# Mikrolysreklamen17.net
KiCad netlist of a schematic drawn in Altium Designer
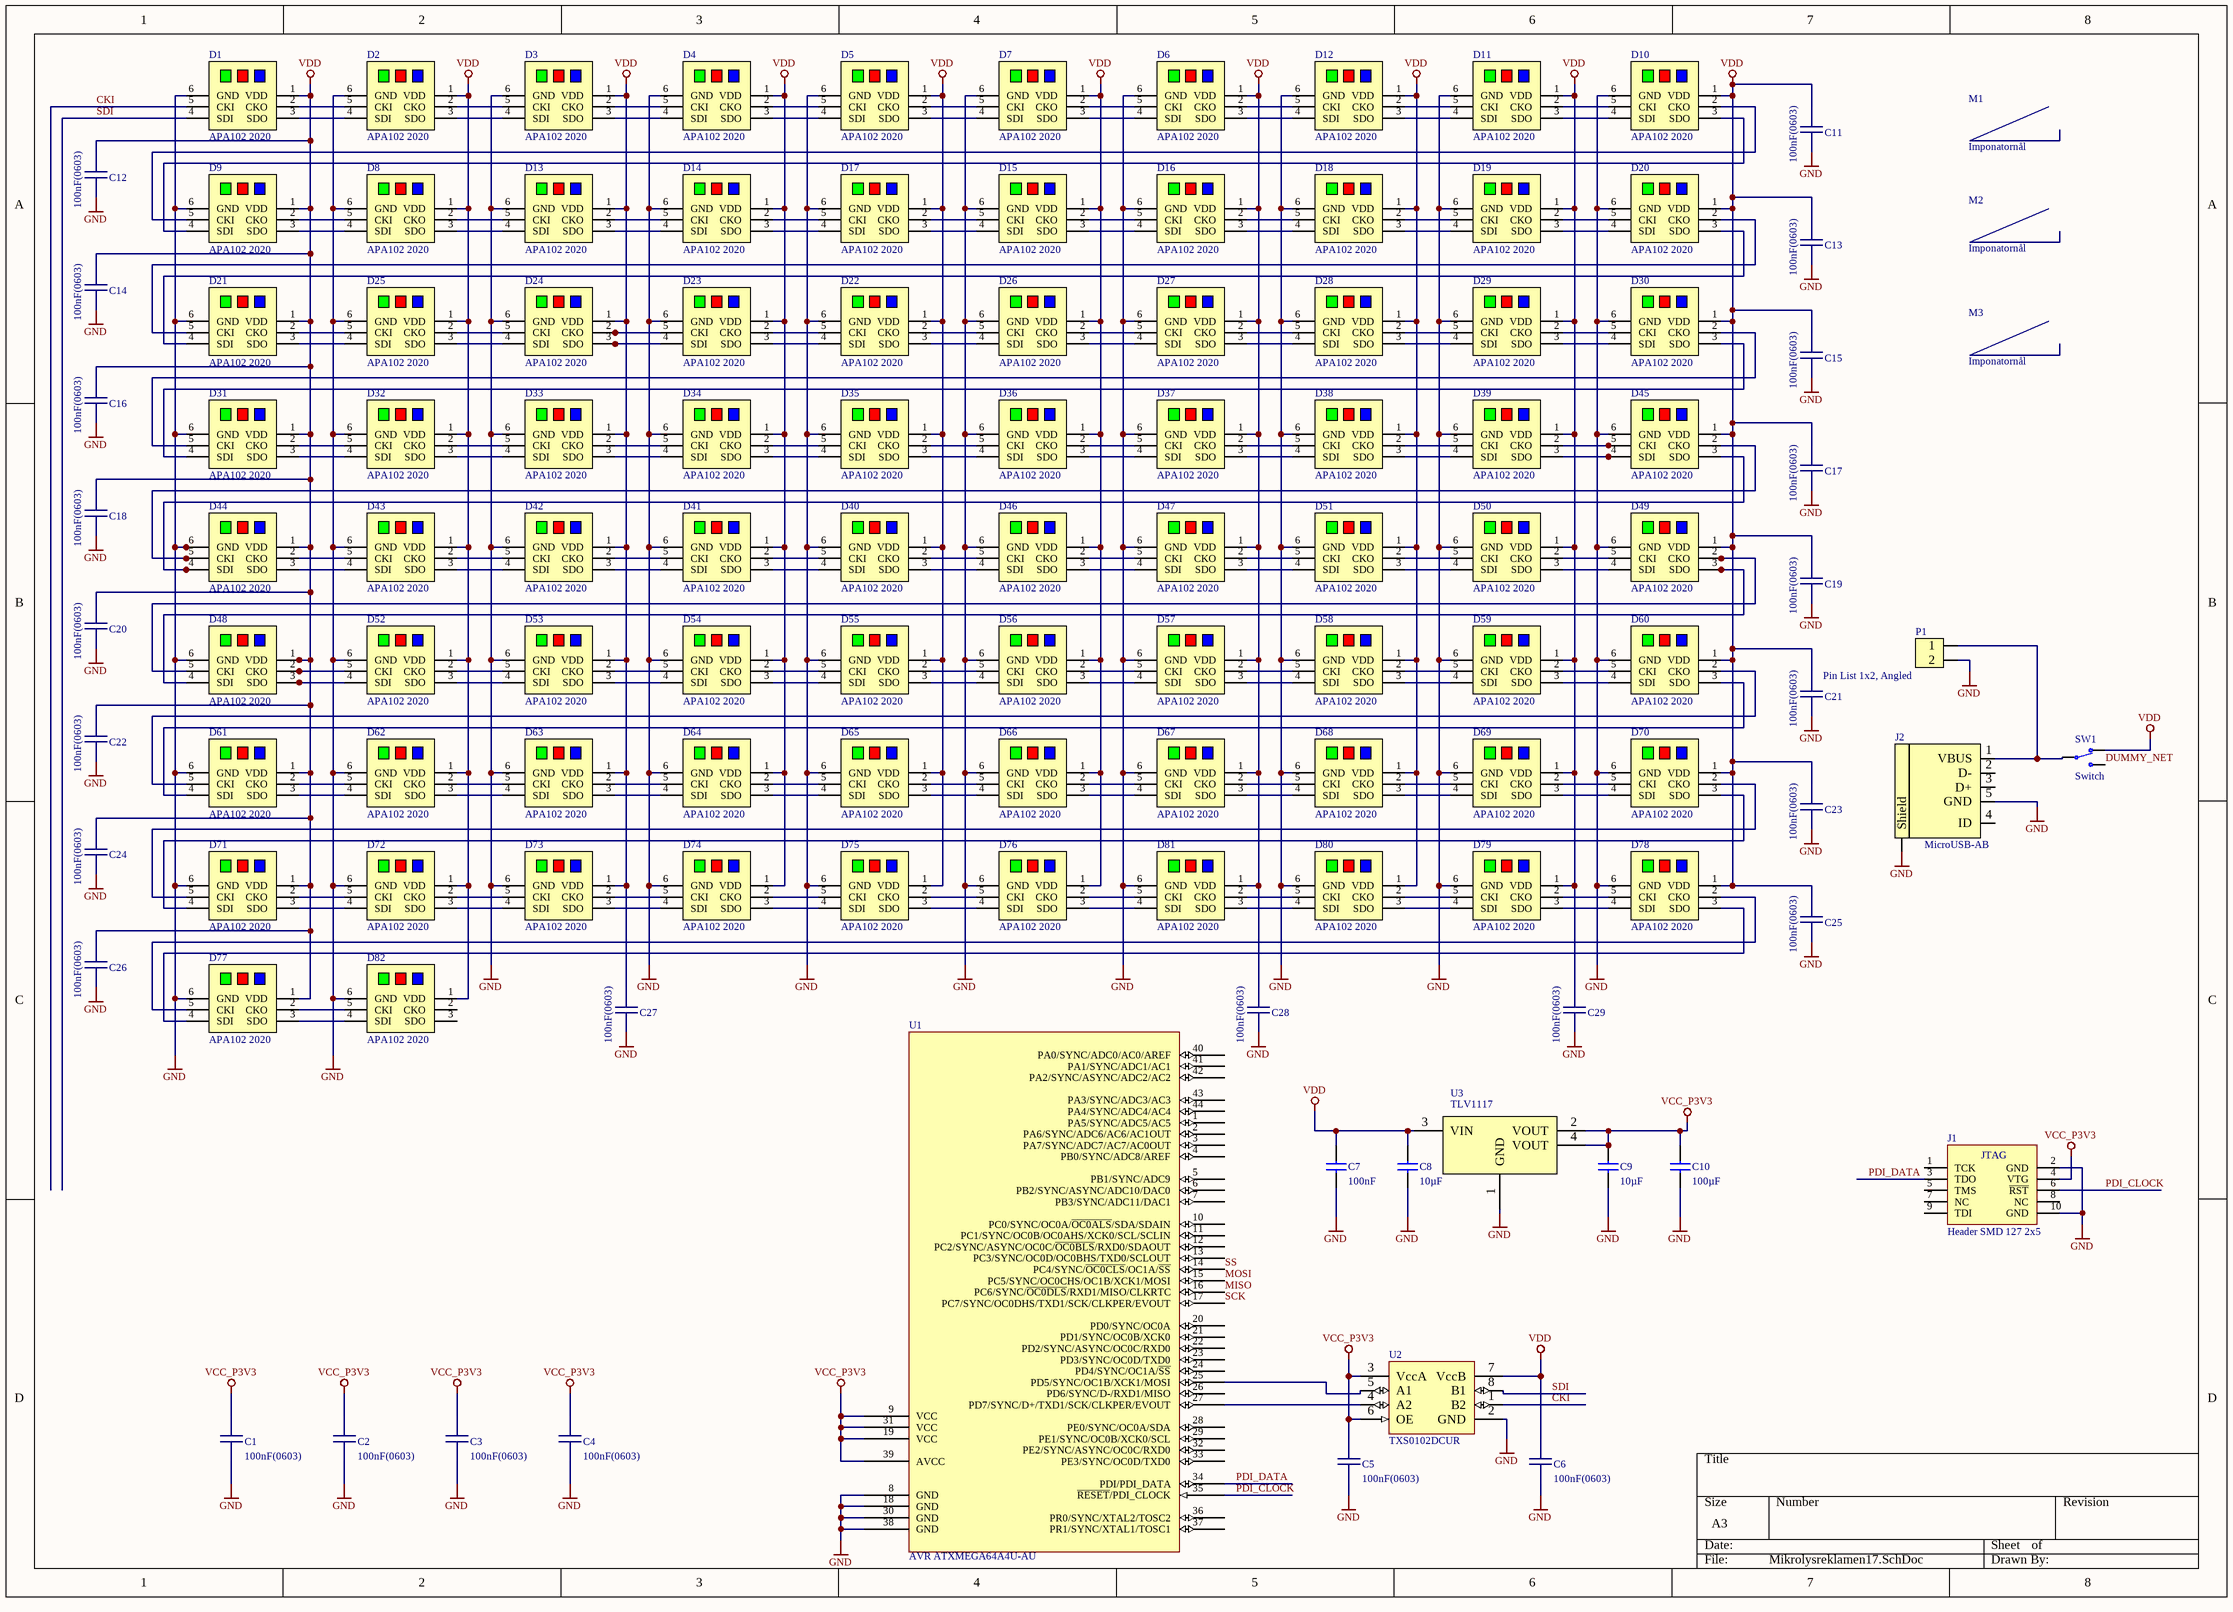
[diagram p0: Mikrolysreklamen17.SchDoc]

(export (version "E")
  (design (tool "Eeschema 10.0.6"))
  (components
    (comp (ref "C1")
      (value "100nF(0603)")
      (footprint "CAPC0603(1608)55_N")
      (description "100nF 0603 5% X7R 50V")
      (libsource (lib "OVLib") (part "CAP"))
    )
    (comp (ref "C2")
      (value "100nF(0603)")
      (footprint "CAPC0603(1608)55_N")
      (description "100nF 0603 5% X7R 50V")
      (libsource (lib "OVLib") (part "CAP"))
    )
    (comp (ref "C3")
      (value "100nF(0603)")
      (footprint "CAPC0603(1608)55_N")
      (description "100nF 0603 5% X7R 50V")
      (libsource (lib "OVLib") (part "CAP"))
    )
    (comp (ref "C4")
      (value "100nF(0603)")
      (footprint "CAPC0603(1608)55_N")
      (description "100nF 0603 5% X7R 50V")
      (libsource (lib "OVLib") (part "CAP"))
    )
    (comp (ref "C5")
      (value "100nF(0603)")
      (footprint "CAPC0603(1608)55_N")
      (description "100nF 0603 5% X7R 50V")
      (libsource (lib "OVLib") (part "CAP"))
    )
    (comp (ref "C6")
      (value "100nF(0603)")
      (footprint "CAPC0603(1608)55_N")
      (description "100nF 0603 5% X7R 50V")
      (libsource (lib "OVLib") (part "CAP"))
    )
    (comp (ref "C7")
      (value "100nF")
      (footprint "CAPC1005X04L")
      (description "Capacitor, X7R, ±10%")
      (fields (field (name "PART NUMBER") "C0402-100n") (field (name "PUBLISHER") "Nordic Semiconductor"))
      (libsource (lib "Nordic Passive DB") (part "CAP"))
    )
    (comp (ref "C8")
      (value "10µF")
      (footprint "CAPC1608X06L")
      (description "Capacitor, X5R, ±20%")
      (fields (field (name "PART NUMBER") "C0603-10µ") (field (name "PUBLISHER") "Nordic Semiconductor"))
      (libsource (lib "Nordic Passive DB") (part "CAP"))
    )
    (comp (ref "C9")
      (value "10µF")
      (footprint "CAPC1608X06L")
      (description "Capacitor, X5R, ±20%")
      (fields (field (name "PART NUMBER") "C0603-10µ") (field (name "PUBLISHER") "Nordic Semiconductor"))
      (libsource (lib "Nordic Passive DB") (part "CAP"))
    )
    (comp (ref "C10")
      (value "100µF")
      (footprint "CAPC2012X11L")
      (description "Chip Cap 0805")
      (fields (field (name "PART NUMBER") "C0805-TBD") (field (name "PUBLISHER") "Nordic Semiconductor"))
      (libsource (lib "Nordic Passive DB") (part "CAP"))
    )
    (comp (ref "C11")
      (value "100nF(0603)")
      (footprint "CAPC0603(1608)55_N")
      (description "100nF 0603 5% X7R 50V")
      (libsource (lib "OVLib_64") (part "CAP"))
    )
    (comp (ref "C12")
      (value "100nF(0603)")
      (footprint "CAPC0603(1608)55_N")
      (description "100nF 0603 5% X7R 50V")
      (libsource (lib "OVLib_64") (part "CAP"))
    )
    (comp (ref "C13")
      (value "100nF(0603)")
      (footprint "CAPC0603(1608)55_N")
      (description "100nF 0603 5% X7R 50V")
      (libsource (lib "OVLib_64") (part "CAP"))
    )
    (comp (ref "C14")
      (value "100nF(0603)")
      (footprint "CAPC0603(1608)55_N")
      (description "100nF 0603 5% X7R 50V")
      (libsource (lib "OVLib_64") (part "CAP"))
    )
    (comp (ref "C15")
      (value "100nF(0603)")
      (footprint "CAPC0603(1608)55_N")
      (description "100nF 0603 5% X7R 50V")
      (libsource (lib "OVLib_64") (part "CAP"))
    )
    (comp (ref "C16")
      (value "100nF(0603)")
      (footprint "CAPC0603(1608)55_N")
      (description "100nF 0603 5% X7R 50V")
      (libsource (lib "OVLib_64") (part "CAP"))
    )
    (comp (ref "C17")
      (value "100nF(0603)")
      (footprint "CAPC0603(1608)55_N")
      (description "100nF 0603 5% X7R 50V")
      (libsource (lib "OVLib_64") (part "CAP"))
    )
    (comp (ref "C18")
      (value "100nF(0603)")
      (footprint "CAPC0603(1608)55_N")
      (description "100nF 0603 5% X7R 50V")
      (libsource (lib "OVLib_64") (part "CAP"))
    )
    (comp (ref "C19")
      (value "100nF(0603)")
      (footprint "CAPC0603(1608)55_N")
      (description "100nF 0603 5% X7R 50V")
      (libsource (lib "OVLib_64") (part "CAP"))
    )
    (comp (ref "C20")
      (value "100nF(0603)")
      (footprint "CAPC0603(1608)55_N")
      (description "100nF 0603 5% X7R 50V")
      (libsource (lib "OVLib_64") (part "CAP"))
    )
    (comp (ref "C21")
      (value "100nF(0603)")
      (footprint "CAPC0603(1608)55_N")
      (description "100nF 0603 5% X7R 50V")
      (libsource (lib "OVLib_64") (part "CAP"))
    )
    (comp (ref "C22")
      (value "100nF(0603)")
      (footprint "CAPC0603(1608)55_N")
      (description "100nF 0603 5% X7R 50V")
      (libsource (lib "OVLib_64") (part "CAP"))
    )
    (comp (ref "C23")
      (value "100nF(0603)")
      (footprint "CAPC0603(1608)55_N")
      (description "100nF 0603 5% X7R 50V")
      (libsource (lib "OVLib_64") (part "CAP"))
    )
    (comp (ref "C24")
      (value "100nF(0603)")
      (footprint "CAPC0603(1608)55_N")
      (description "100nF 0603 5% X7R 50V")
      (libsource (lib "OVLib_64") (part "CAP"))
    )
    (comp (ref "C25")
      (value "100nF(0603)")
      (footprint "CAPC0603(1608)55_N")
      (description "100nF 0603 5% X7R 50V")
      (libsource (lib "OVLib_64") (part "CAP"))
    )
    (comp (ref "C26")
      (value "100nF(0603)")
      (footprint "CAPC0603(1608)55_N")
      (description "100nF 0603 5% X7R 50V")
      (libsource (lib "OVLib_64") (part "CAP"))
    )
    (comp (ref "C27")
      (value "100nF(0603)")
      (footprint "CAPC0603(1608)55_N")
      (description "100nF 0603 5% X7R 50V")
      (libsource (lib "OVLib_64") (part "CAP"))
    )
    (comp (ref "C28")
      (value "100nF(0603)")
      (footprint "CAPC0603(1608)55_N")
      (description "100nF 0603 5% X7R 50V")
      (libsource (lib "OVLib_64") (part "CAP"))
    )
    (comp (ref "C29")
      (value "100nF(0603)")
      (footprint "CAPC0603(1608)55_N")
      (description "100nF 0603 5% X7R 50V")
      (libsource (lib "OVLib_64") (part "CAP"))
    )
    (comp (ref "D1")
      (value "APA102 2020")
      (footprint "PCBComponent_1")
      (libsource (lib "Schlib1") (part "APA102_2020"))
    )
    (comp (ref "D2")
      (value "APA102 2020")
      (footprint "PCBComponent_1")
      (libsource (lib "Schlib1") (part "APA102_2020"))
    )
    (comp (ref "D3")
      (value "APA102 2020")
      (footprint "PCBComponent_1")
      (libsource (lib "Schlib1") (part "APA102_2020"))
    )
    (comp (ref "D4")
      (value "APA102 2020")
      (footprint "PCBComponent_1")
      (libsource (lib "Schlib1") (part "APA102_2020"))
    )
    (comp (ref "D5")
      (value "APA102 2020")
      (footprint "PCBComponent_1")
      (libsource (lib "Schlib1") (part "APA102_2020"))
    )
    (comp (ref "D6")
      (value "APA102 2020")
      (footprint "PCBComponent_1")
      (libsource (lib "Schlib1") (part "APA102_2020"))
    )
    (comp (ref "D7")
      (value "APA102 2020")
      (footprint "PCBComponent_1")
      (libsource (lib "Schlib1") (part "APA102_2020"))
    )
    (comp (ref "D8")
      (value "APA102 2020")
      (footprint "PCBComponent_1")
      (libsource (lib "Schlib1") (part "APA102_2020"))
    )
    (comp (ref "D9")
      (value "APA102 2020")
      (footprint "PCBComponent_1")
      (libsource (lib "Schlib1") (part "APA102_2020"))
    )
    (comp (ref "D10")
      (value "APA102 2020")
      (footprint "PCBComponent_1")
      (libsource (lib "Schlib1") (part "APA102_2020"))
    )
    (comp (ref "D11")
      (value "APA102 2020")
      (footprint "PCBComponent_1")
      (libsource (lib "Schlib1") (part "APA102_2020"))
    )
    (comp (ref "D12")
      (value "APA102 2020")
      (footprint "PCBComponent_1")
      (libsource (lib "Schlib1") (part "APA102_2020"))
    )
    (comp (ref "D13")
      (value "APA102 2020")
      (footprint "PCBComponent_1")
      (libsource (lib "Schlib1") (part "APA102_2020"))
    )
    (comp (ref "D14")
      (value "APA102 2020")
      (footprint "PCBComponent_1")
      (libsource (lib "Schlib1") (part "APA102_2020"))
    )
    (comp (ref "D15")
      (value "APA102 2020")
      (footprint "PCBComponent_1")
      (libsource (lib "Schlib1") (part "APA102_2020"))
    )
    (comp (ref "D16")
      (value "APA102 2020")
      (footprint "PCBComponent_1")
      (libsource (lib "Schlib1") (part "APA102_2020"))
    )
    (comp (ref "D17")
      (value "APA102 2020")
      (footprint "PCBComponent_1")
      (libsource (lib "Schlib1") (part "APA102_2020"))
    )
    (comp (ref "D18")
      (value "APA102 2020")
      (footprint "PCBComponent_1")
      (libsource (lib "Schlib1") (part "APA102_2020"))
    )
    (comp (ref "D19")
      (value "APA102 2020")
      (footprint "PCBComponent_1")
      (libsource (lib "Schlib1") (part "APA102_2020"))
    )
    (comp (ref "D20")
      (value "APA102 2020")
      (footprint "PCBComponent_1")
      (libsource (lib "Schlib1") (part "APA102_2020"))
    )
    (comp (ref "D21")
      (value "APA102 2020")
      (footprint "PCBComponent_1")
      (libsource (lib "Schlib1") (part "APA102_2020"))
    )
    (comp (ref "D22")
      (value "APA102 2020")
      (footprint "PCBComponent_1")
      (libsource (lib "Schlib1") (part "APA102_2020"))
    )
    (comp (ref "D23")
      (value "APA102 2020")
      (footprint "PCBComponent_1")
      (libsource (lib "Schlib1") (part "APA102_2020"))
    )
    (comp (ref "D24")
      (value "APA102 2020")
      (footprint "PCBComponent_1")
      (libsource (lib "Schlib1") (part "APA102_2020"))
    )
    (comp (ref "D25")
      (value "APA102 2020")
      (footprint "PCBComponent_1")
      (libsource (lib "Schlib1") (part "APA102_2020"))
    )
    (comp (ref "D26")
      (value "APA102 2020")
      (footprint "PCBComponent_1")
      (libsource (lib "Schlib1") (part "APA102_2020"))
    )
    (comp (ref "D27")
      (value "APA102 2020")
      (footprint "PCBComponent_1")
      (libsource (lib "Schlib1") (part "APA102_2020"))
    )
    (comp (ref "D28")
      (value "APA102 2020")
      (footprint "PCBComponent_1")
      (libsource (lib "Schlib1") (part "APA102_2020"))
    )
    (comp (ref "D29")
      (value "APA102 2020")
      (footprint "PCBComponent_1")
      (libsource (lib "Schlib1") (part "APA102_2020"))
    )
    (comp (ref "D30")
      (value "APA102 2020")
      (footprint "PCBComponent_1")
      (libsource (lib "Schlib1") (part "APA102_2020"))
    )
    (comp (ref "D31")
      (value "APA102 2020")
      (footprint "PCBComponent_1")
      (libsource (lib "Schlib1") (part "APA102_2020"))
    )
    (comp (ref "D32")
      (value "APA102 2020")
      (footprint "PCBComponent_1")
      (libsource (lib "Schlib1") (part "APA102_2020"))
    )
    (comp (ref "D33")
      (value "APA102 2020")
      (footprint "PCBComponent_1")
      (libsource (lib "Schlib1") (part "APA102_2020"))
    )
    (comp (ref "D34")
      (value "APA102 2020")
      (footprint "PCBComponent_1")
      (libsource (lib "Schlib1") (part "APA102_2020"))
    )
    (comp (ref "D35")
      (value "APA102 2020")
      (footprint "PCBComponent_1")
      (libsource (lib "Schlib1") (part "APA102_2020"))
    )
    (comp (ref "D36")
      (value "APA102 2020")
      (footprint "PCBComponent_1")
      (libsource (lib "Schlib1") (part "APA102_2020"))
    )
    (comp (ref "D37")
      (value "APA102 2020")
      (footprint "PCBComponent_1")
      (libsource (lib "Schlib1") (part "APA102_2020"))
    )
    (comp (ref "D38")
      (value "APA102 2020")
      (footprint "PCBComponent_1")
      (libsource (lib "Schlib1") (part "APA102_2020"))
    )
    (comp (ref "D39")
      (value "APA102 2020")
      (footprint "PCBComponent_1")
      (libsource (lib "Schlib1") (part "APA102_2020"))
    )
    (comp (ref "D40")
      (value "APA102 2020")
      (footprint "PCBComponent_1")
      (libsource (lib "Schlib1") (part "APA102_2020"))
    )
    (comp (ref "D41")
      (value "APA102 2020")
      (footprint "PCBComponent_1")
      (libsource (lib "Schlib1") (part "APA102_2020"))
    )
    (comp (ref "D42")
      (value "APA102 2020")
      (footprint "PCBComponent_1")
      (libsource (lib "Schlib1") (part "APA102_2020"))
    )
    (comp (ref "D43")
      (value "APA102 2020")
      (footprint "PCBComponent_1")
      (libsource (lib "Schlib1") (part "APA102_2020"))
    )
    (comp (ref "D44")
      (value "APA102 2020")
      (footprint "PCBComponent_1")
      (libsource (lib "Schlib1") (part "APA102_2020"))
    )
    (comp (ref "D45")
      (value "APA102 2020")
      (footprint "PCBComponent_1")
      (libsource (lib "Schlib1") (part "APA102_2020"))
    )
    (comp (ref "D46")
      (value "APA102 2020")
      (footprint "PCBComponent_1")
      (libsource (lib "Schlib1") (part "APA102_2020"))
    )
    (comp (ref "D47")
      (value "APA102 2020")
      (footprint "PCBComponent_1")
      (libsource (lib "Schlib1") (part "APA102_2020"))
    )
    (comp (ref "D48")
      (value "APA102 2020")
      (footprint "PCBComponent_1")
      (libsource (lib "Schlib1") (part "APA102_2020"))
    )
    (comp (ref "D49")
      (value "APA102 2020")
      (footprint "PCBComponent_1")
      (libsource (lib "Schlib1") (part "APA102_2020"))
    )
    (comp (ref "D50")
      (value "APA102 2020")
      (footprint "PCBComponent_1")
      (libsource (lib "Schlib1") (part "APA102_2020"))
    )
    (comp (ref "D51")
      (value "APA102 2020")
      (footprint "PCBComponent_1")
      (libsource (lib "Schlib1") (part "APA102_2020"))
    )
    (comp (ref "D52")
      (value "APA102 2020")
      (footprint "PCBComponent_1")
      (libsource (lib "Schlib1") (part "APA102_2020"))
    )
    (comp (ref "D53")
      (value "APA102 2020")
      (footprint "PCBComponent_1")
      (libsource (lib "Schlib1") (part "APA102_2020"))
    )
    (comp (ref "D54")
      (value "APA102 2020")
      (footprint "PCBComponent_1")
      (libsource (lib "Schlib1") (part "APA102_2020"))
    )
    (comp (ref "D55")
      (value "APA102 2020")
      (footprint "PCBComponent_1")
      (libsource (lib "Schlib1") (part "APA102_2020"))
    )
    (comp (ref "D56")
      (value "APA102 2020")
      (footprint "PCBComponent_1")
      (libsource (lib "Schlib1") (part "APA102_2020"))
    )
    (comp (ref "D57")
      (value "APA102 2020")
      (footprint "PCBComponent_1")
      (libsource (lib "Schlib1") (part "APA102_2020"))
    )
    (comp (ref "D58")
      (value "APA102 2020")
      (footprint "PCBComponent_1")
      (libsource (lib "Schlib1") (part "APA102_2020"))
    )
    (comp (ref "D59")
      (value "APA102 2020")
      (footprint "PCBComponent_1")
      (libsource (lib "Schlib1") (part "APA102_2020"))
    )
    (comp (ref "D60")
      (value "APA102 2020")
      (footprint "PCBComponent_1")
      (libsource (lib "Schlib1") (part "APA102_2020"))
    )
    (comp (ref "D61")
      (value "APA102 2020")
      (footprint "PCBComponent_1")
      (libsource (lib "Schlib1") (part "APA102_2020"))
    )
    (comp (ref "D62")
      (value "APA102 2020")
      (footprint "PCBComponent_1")
      (libsource (lib "Schlib1") (part "APA102_2020"))
    )
    (comp (ref "D63")
      (value "APA102 2020")
      (footprint "PCBComponent_1")
      (libsource (lib "Schlib1") (part "APA102_2020"))
    )
    (comp (ref "D64")
      (value "APA102 2020")
      (footprint "PCBComponent_1")
      (libsource (lib "Schlib1") (part "APA102_2020"))
    )
    (comp (ref "D65")
      (value "APA102 2020")
      (footprint "PCBComponent_1")
      (libsource (lib "Schlib1") (part "APA102_2020"))
    )
    (comp (ref "D66")
      (value "APA102 2020")
      (footprint "PCBComponent_1")
      (libsource (lib "Schlib1") (part "APA102_2020"))
    )
    (comp (ref "D67")
      (value "APA102 2020")
      (footprint "PCBComponent_1")
      (libsource (lib "Schlib1") (part "APA102_2020"))
    )
    (comp (ref "D68")
      (value "APA102 2020")
      (footprint "PCBComponent_1")
      (libsource (lib "Schlib1") (part "APA102_2020"))
    )
    (comp (ref "D69")
      (value "APA102 2020")
      (footprint "PCBComponent_1")
      (libsource (lib "Schlib1") (part "APA102_2020"))
    )
    (comp (ref "D70")
      (value "APA102 2020")
      (footprint "PCBComponent_1")
      (libsource (lib "Schlib1") (part "APA102_2020"))
    )
    (comp (ref "D71")
      (value "APA102 2020")
      (footprint "PCBComponent_1")
      (libsource (lib "Schlib1") (part "APA102_2020"))
    )
    (comp (ref "D72")
      (value "APA102 2020")
      (footprint "PCBComponent_1")
      (libsource (lib "Schlib1") (part "APA102_2020"))
    )
    (comp (ref "D73")
      (value "APA102 2020")
      (footprint "PCBComponent_1")
      (libsource (lib "Schlib1") (part "APA102_2020"))
    )
    (comp (ref "D74")
      (value "APA102 2020")
      (footprint "PCBComponent_1")
      (libsource (lib "Schlib1") (part "APA102_2020"))
    )
    (comp (ref "D75")
      (value "APA102 2020")
      (footprint "PCBComponent_1")
      (libsource (lib "Schlib1") (part "APA102_2020"))
    )
    (comp (ref "D76")
      (value "APA102 2020")
      (footprint "PCBComponent_1")
      (libsource (lib "Schlib1") (part "APA102_2020"))
    )
    (comp (ref "D77")
      (value "APA102 2020")
      (footprint "PCBComponent_1")
      (libsource (lib "Schlib1") (part "APA102_2020"))
    )
    (comp (ref "D78")
      (value "APA102 2020")
      (footprint "PCBComponent_1")
      (libsource (lib "Schlib1") (part "APA102_2020"))
    )
    (comp (ref "D79")
      (value "APA102 2020")
      (footprint "PCBComponent_1")
      (libsource (lib "Schlib1") (part "APA102_2020"))
    )
    (comp (ref "D80")
      (value "APA102 2020")
      (footprint "PCBComponent_1")
      (libsource (lib "Schlib1") (part "APA102_2020"))
    )
    (comp (ref "D81")
      (value "APA102 2020")
      (footprint "PCBComponent_1")
      (libsource (lib "Schlib1") (part "APA102_2020"))
    )
    (comp (ref "D82")
      (value "APA102 2020")
      (footprint "PCBComponent_1")
      (libsource (lib "Schlib1") (part "APA102_2020"))
    )
    (comp (ref "J1")
      (value "Header SMD 127 2x5")
      (footprint "SMDHDRV10P127_2X5_615X330X560B")
      (description "1,27mm Pitch SMD Header")
      (libsource (lib "OVLib") (part "AVRJTAG"))
    )
    (comp (ref "J2")
      (value "MicroUSB-AB")
      (footprint "FCI_10104111-0001LF")
      (description "MicroUSB-AB-SMT")
      (fields
        (field (name "PART NUMBER") "FCI 10104111-0001LF")
        (field (name "MANUFACTURER") "FCI")
        (field (name "PUBLISHER") "Nordic Semiconductor")
      )
      (libsource (lib "Nordic Passive DB") (part "MiniUSB-AB-SMT"))
    )
    (comp (ref "M1")
      (value "Imponatornål")
      (footprint "Imponatornaal_liten")
      (description "nål til imponatorplate 20mm (Brooch back)")
      (libsource (lib "OVLib_64") (part "Imponatornaal"))
    )
    (comp (ref "M2")
      (value "Imponatornål")
      (footprint "Imponatornaal_liten")
      (description "nål til imponatorplate 20mm (Brooch back)")
      (libsource (lib "OVLib_64") (part "Imponatornaal"))
    )
    (comp (ref "M3")
      (value "Imponatornål")
      (footprint "Imponatornaal_liten")
      (description "nål til imponatorplate 20mm (Brooch back)")
      (libsource (lib "OVLib_64") (part "Imponatornaal"))
    )
    (comp (ref "P1")
      (value "Pin List 1x2, Angled")
      (footprint "LIST_ANG_1x2-SMD-2.54MM")
      (description "Pin List 1x2, 2.54mm (100mil), Right Angled, SMD")
      (fields
        (field (name "PART NUMBER") "Pin List Ang 1x2 SMD, 2.54mm")
        (field (name "MANUFACTURER") "W-CON")
        (field (name "PUBLISHER") "Nordic Semiconductor")
      )
      (libsource (lib "Nordic Passive DB") (part "CONN-2"))
    )
    (comp (ref "SW1")
      (value "Switch")
      (footprint "JS102011SAQN")
      (description "SMD slide Switch (ON-ON)")
      (fields
        (field (name "PART NUMBER") "JS102011SAQN")
        (field (name "MANUFACTURER") "C&K Components")
        (field (name "PUBLISHER") "Nordic Semiconductor")
      )
      (libsource (lib "Nordic Discrete DB") (part "SW-SPDT"))
    )
    (comp (ref "U1")
      (value "AVR ATXMEGA64A4U-AU")
      (footprint "TQFP80P1200X1200X120-44N")
      (description "Mikrokontroller")
      (libsource (lib "OVLib") (part "ATXMEGA-A4U"))
    )
    (comp (ref "U2")
      (value "TXS0102DCUR")
      (footprint "TSSOP50P310X90-8N")
      (description "IC VOLT-LEVEL TRANSLATOR 8-US8")
      (fields
        (field (name "MANUFACTURER") "Texas Instruments")
        (field (name "PUBLISHER") "Nordic Semiconductor")
      )
      (libsource (lib "Nordic Active DB") (part "TXS0102DC"))
    )
    (comp (ref "U3")
      (value "TLV1117")
      (footprint "SOT230P700X180-4N")
      (description "REG LDO 3.3V 0.8A SOT223")
      (fields
        (field (name "PART NUMBER") "TLV1117-33CDCYR")
        (field (name "MANUFACTURER") "Texas Instruments")
        (field (name "PUBLISHER") "Nordic Semiconductor")
      )
      (libsource (lib "Nordic Active DB") (part "LD1117_fixed"))
    )
  )
  (nets
    (net (code "1") (name "/CKI") (class "Default")
      (node (ref "D1") (pin "5") (pinfunction "CKI_5") (pintype "passive"))
      (node (ref "U2") (pin "1") (pinfunction "B2_1") (pintype "bidirectional"))
    )
    (net (code "2") (name "/DUMMY_NET") (class "Default")
      (node (ref "SW1") (pin "3") (pinfunction "N.O_3") (pintype "passive"))
    )
    (net (code "3") (name "/MISO") (class "Default")
      (node (ref "U1") (pin "16") (pinfunction "PC6/SYNC/~{OC0DLS}/RXD1/MISO/CLKRTC_16") (pintype "bidirectional"))
    )
    (net (code "4") (name "/MOSI") (class "Default")
      (node (ref "U1") (pin "15") (pinfunction "PC5/SYNC/OC0CHS/OC1B/XCK1/MOSI_15") (pintype "bidirectional"))
    )
    (net (code "5") (name "/PDI_CLOCK") (class "Default")
      (node (ref "J1") (pin "6") (pinfunction "~{RST}_6") (pintype "passive"))
      (node (ref "U1") (pin "35") (pinfunction "~{RESET}/PDI_CLOCK_35") (pintype "input"))
    )
    (net (code "6") (name "/PDI_DATA") (class "Default")
      (node (ref "J1") (pin "3") (pinfunction "TDO_3") (pintype "passive"))
      (node (ref "U1") (pin "34") (pinfunction "PDI/PDI_DATA_34") (pintype "bidirectional"))
    )
    (net (code "7") (name "/SCK") (class "Default")
      (node (ref "U1") (pin "17") (pinfunction "PC7/SYNC/OC0DHS/TXD1/SCK/CLKPER/EVOUT_17") (pintype "bidirectional"))
    )
    (net (code "8") (name "/SDI") (class "Default")
      (node (ref "D1") (pin "4") (pinfunction "SDI_4") (pintype "passive"))
      (node (ref "U2") (pin "8") (pinfunction "B1_8") (pintype "bidirectional"))
    )
    (net (code "9") (name "/SS") (class "Default")
      (node (ref "U1") (pin "14") (pinfunction "PC4/SYNC/~{OC0CLS}/OC1A/~{SS}_14") (pintype "bidirectional"))
    )
    (net (code "10") (name "GND") (class "Default")
      (node (ref "C1") (pin "1") (pinfunction "1_1") (pintype "passive"))
      (node (ref "C10") (pin "1") (pinfunction "1_1") (pintype "passive"))
      (node (ref "C11") (pin "1") (pinfunction "1_1") (pintype "passive"))
      (node (ref "C12") (pin "1") (pinfunction "1_1") (pintype "passive"))
      (node (ref "C13") (pin "1") (pinfunction "1_1") (pintype "passive"))
      (node (ref "C14") (pin "1") (pinfunction "1_1") (pintype "passive"))
      (node (ref "C15") (pin "1") (pinfunction "1_1") (pintype "passive"))
      (node (ref "C16") (pin "1") (pinfunction "1_1") (pintype "passive"))
      (node (ref "C17") (pin "1") (pinfunction "1_1") (pintype "passive"))
      (node (ref "C18") (pin "1") (pinfunction "1_1") (pintype "passive"))
      (node (ref "C19") (pin "1") (pinfunction "1_1") (pintype "passive"))
      (node (ref "C2") (pin "1") (pinfunction "1_1") (pintype "passive"))
      (node (ref "C20") (pin "1") (pinfunction "1_1") (pintype "passive"))
      (node (ref "C21") (pin "1") (pinfunction "1_1") (pintype "passive"))
      (node (ref "C22") (pin "1") (pinfunction "1_1") (pintype "passive"))
      (node (ref "C23") (pin "1") (pinfunction "1_1") (pintype "passive"))
      (node (ref "C24") (pin "1") (pinfunction "1_1") (pintype "passive"))
      (node (ref "C25") (pin "1") (pinfunction "1_1") (pintype "passive"))
      (node (ref "C26") (pin "1") (pinfunction "1_1") (pintype "passive"))
      (node (ref "C27") (pin "1") (pinfunction "1_1") (pintype "passive"))
      (node (ref "C28") (pin "1") (pinfunction "1_1") (pintype "passive"))
      (node (ref "C29") (pin "1") (pinfunction "1_1") (pintype "passive"))
      (node (ref "C3") (pin "1") (pinfunction "1_1") (pintype "passive"))
      (node (ref "C4") (pin "1") (pinfunction "1_1") (pintype "passive"))
      (node (ref "C5") (pin "1") (pinfunction "1_1") (pintype "passive"))
      (node (ref "C6") (pin "1") (pinfunction "1_1") (pintype "passive"))
      (node (ref "C7") (pin "1") (pinfunction "1_1") (pintype "passive"))
      (node (ref "C8") (pin "1") (pinfunction "1_1") (pintype "passive"))
      (node (ref "C9") (pin "1") (pinfunction "1_1") (pintype "passive"))
      (node (ref "D1") (pin "6") (pinfunction "GND_6") (pintype "passive"))
      (node (ref "D10") (pin "6") (pinfunction "GND_6") (pintype "passive"))
      (node (ref "D11") (pin "6") (pinfunction "GND_6") (pintype "passive"))
      (node (ref "D12") (pin "6") (pinfunction "GND_6") (pintype "passive"))
      (node (ref "D13") (pin "6") (pinfunction "GND_6") (pintype "passive"))
      (node (ref "D14") (pin "6") (pinfunction "GND_6") (pintype "passive"))
      (node (ref "D15") (pin "6") (pinfunction "GND_6") (pintype "passive"))
      (node (ref "D16") (pin "6") (pinfunction "GND_6") (pintype "passive"))
      (node (ref "D17") (pin "6") (pinfunction "GND_6") (pintype "passive"))
      (node (ref "D18") (pin "6") (pinfunction "GND_6") (pintype "passive"))
      (node (ref "D19") (pin "6") (pinfunction "GND_6") (pintype "passive"))
      (node (ref "D2") (pin "6") (pinfunction "GND_6") (pintype "passive"))
      (node (ref "D20") (pin "6") (pinfunction "GND_6") (pintype "passive"))
      (node (ref "D21") (pin "6") (pinfunction "GND_6") (pintype "passive"))
      (node (ref "D22") (pin "6") (pinfunction "GND_6") (pintype "passive"))
      (node (ref "D23") (pin "6") (pinfunction "GND_6") (pintype "passive"))
      (node (ref "D24") (pin "6") (pinfunction "GND_6") (pintype "passive"))
      (node (ref "D25") (pin "6") (pinfunction "GND_6") (pintype "passive"))
      (node (ref "D26") (pin "6") (pinfunction "GND_6") (pintype "passive"))
      (node (ref "D27") (pin "6") (pinfunction "GND_6") (pintype "passive"))
      (node (ref "D28") (pin "6") (pinfunction "GND_6") (pintype "passive"))
      (node (ref "D29") (pin "6") (pinfunction "GND_6") (pintype "passive"))
      (node (ref "D3") (pin "6") (pinfunction "GND_6") (pintype "passive"))
      (node (ref "D30") (pin "6") (pinfunction "GND_6") (pintype "passive"))
      (node (ref "D31") (pin "6") (pinfunction "GND_6") (pintype "passive"))
      (node (ref "D32") (pin "6") (pinfunction "GND_6") (pintype "passive"))
      (node (ref "D33") (pin "6") (pinfunction "GND_6") (pintype "passive"))
      (node (ref "D34") (pin "6") (pinfunction "GND_6") (pintype "passive"))
      (node (ref "D35") (pin "6") (pinfunction "GND_6") (pintype "passive"))
      (node (ref "D36") (pin "6") (pinfunction "GND_6") (pintype "passive"))
      (node (ref "D37") (pin "6") (pinfunction "GND_6") (pintype "passive"))
      (node (ref "D38") (pin "6") (pinfunction "GND_6") (pintype "passive"))
      (node (ref "D39") (pin "6") (pinfunction "GND_6") (pintype "passive"))
      (node (ref "D4") (pin "6") (pinfunction "GND_6") (pintype "passive"))
      (node (ref "D40") (pin "6") (pinfunction "GND_6") (pintype "passive"))
      (node (ref "D41") (pin "6") (pinfunction "GND_6") (pintype "passive"))
      (node (ref "D42") (pin "6") (pinfunction "GND_6") (pintype "passive"))
      (node (ref "D43") (pin "6") (pinfunction "GND_6") (pintype "passive"))
      (node (ref "D44") (pin "6") (pinfunction "GND_6") (pintype "passive"))
      (node (ref "D45") (pin "6") (pinfunction "GND_6") (pintype "passive"))
      (node (ref "D46") (pin "6") (pinfunction "GND_6") (pintype "passive"))
      (node (ref "D47") (pin "6") (pinfunction "GND_6") (pintype "passive"))
      (node (ref "D48") (pin "6") (pinfunction "GND_6") (pintype "passive"))
      (node (ref "D49") (pin "6") (pinfunction "GND_6") (pintype "passive"))
      (node (ref "D5") (pin "6") (pinfunction "GND_6") (pintype "passive"))
      (node (ref "D50") (pin "6") (pinfunction "GND_6") (pintype "passive"))
      (node (ref "D51") (pin "6") (pinfunction "GND_6") (pintype "passive"))
      (node (ref "D52") (pin "6") (pinfunction "GND_6") (pintype "passive"))
      (node (ref "D53") (pin "6") (pinfunction "GND_6") (pintype "passive"))
      (node (ref "D54") (pin "6") (pinfunction "GND_6") (pintype "passive"))
      (node (ref "D55") (pin "6") (pinfunction "GND_6") (pintype "passive"))
      (node (ref "D56") (pin "6") (pinfunction "GND_6") (pintype "passive"))
      (node (ref "D57") (pin "6") (pinfunction "GND_6") (pintype "passive"))
      (node (ref "D58") (pin "6") (pinfunction "GND_6") (pintype "passive"))
      (node (ref "D59") (pin "6") (pinfunction "GND_6") (pintype "passive"))
      (node (ref "D6") (pin "6") (pinfunction "GND_6") (pintype "passive"))
      (node (ref "D60") (pin "6") (pinfunction "GND_6") (pintype "passive"))
      (node (ref "D61") (pin "6") (pinfunction "GND_6") (pintype "passive"))
      (node (ref "D62") (pin "6") (pinfunction "GND_6") (pintype "passive"))
      (node (ref "D63") (pin "6") (pinfunction "GND_6") (pintype "passive"))
      (node (ref "D64") (pin "6") (pinfunction "GND_6") (pintype "passive"))
      (node (ref "D65") (pin "6") (pinfunction "GND_6") (pintype "passive"))
      (node (ref "D66") (pin "6") (pinfunction "GND_6") (pintype "passive"))
      (node (ref "D67") (pin "6") (pinfunction "GND_6") (pintype "passive"))
      (node (ref "D68") (pin "6") (pinfunction "GND_6") (pintype "passive"))
      (node (ref "D69") (pin "6") (pinfunction "GND_6") (pintype "passive"))
      (node (ref "D7") (pin "6") (pinfunction "GND_6") (pintype "passive"))
      (node (ref "D70") (pin "6") (pinfunction "GND_6") (pintype "passive"))
      (node (ref "D71") (pin "6") (pinfunction "GND_6") (pintype "passive"))
      (node (ref "D72") (pin "6") (pinfunction "GND_6") (pintype "passive"))
      (node (ref "D73") (pin "6") (pinfunction "GND_6") (pintype "passive"))
      (node (ref "D74") (pin "6") (pinfunction "GND_6") (pintype "passive"))
      (node (ref "D75") (pin "6") (pinfunction "GND_6") (pintype "passive"))
      (node (ref "D76") (pin "6") (pinfunction "GND_6") (pintype "passive"))
      (node (ref "D77") (pin "6") (pinfunction "GND_6") (pintype "passive"))
      (node (ref "D78") (pin "6") (pinfunction "GND_6") (pintype "passive"))
      (node (ref "D79") (pin "6") (pinfunction "GND_6") (pintype "passive"))
      (node (ref "D8") (pin "6") (pinfunction "GND_6") (pintype "passive"))
      (node (ref "D80") (pin "6") (pinfunction "GND_6") (pintype "passive"))
      (node (ref "D81") (pin "6") (pinfunction "GND_6") (pintype "passive"))
      (node (ref "D82") (pin "6") (pinfunction "GND_6") (pintype "passive"))
      (node (ref "D9") (pin "6") (pinfunction "GND_6") (pintype "passive"))
      (node (ref "J1") (pin "10") (pinfunction "GND_10") (pintype "passive"))
      (node (ref "J1") (pin "2") (pinfunction "GND_2") (pintype "passive"))
      (node (ref "J2") (pin "5") (pinfunction "GND_5") (pintype "power_in"))
      (node (ref "J2") (pin "6") (pinfunction "Shield_6") (pintype "power_in"))
      (node (ref "P1") (pin "2") (pinfunction "2_2") (pintype "passive"))
      (node (ref "U1") (pin "18") (pinfunction "GND_18") (pintype "power_in"))
      (node (ref "U1") (pin "30") (pinfunction "GND_30") (pintype "power_in"))
      (node (ref "U1") (pin "38") (pinfunction "GND_38") (pintype "power_in"))
      (node (ref "U1") (pin "8") (pinfunction "GND_8") (pintype "power_in"))
      (node (ref "U2") (pin "2") (pinfunction "GND_2") (pintype "power_in"))
      (node (ref "U3") (pin "1") (pinfunction "GND_1") (pintype "power_in"))
    )
    (net (code "11") (name "Net-(D1-CKO)") (class "Default")
      (node (ref "D1") (pin "2") (pinfunction "CKO_2") (pintype "passive"))
      (node (ref "D2") (pin "5") (pinfunction "CKI_5") (pintype "passive"))
    )
    (net (code "12") (name "Net-(D1-SDO)") (class "Default")
      (node (ref "D1") (pin "3") (pinfunction "SDO_3") (pintype "passive"))
      (node (ref "D2") (pin "4") (pinfunction "SDI_4") (pintype "passive"))
    )
    (net (code "13") (name "Net-(D2-CKO)") (class "Default")
      (node (ref "D2") (pin "2") (pinfunction "CKO_2") (pintype "passive"))
      (node (ref "D3") (pin "5") (pinfunction "CKI_5") (pintype "passive"))
    )
    (net (code "14") (name "Net-(D2-SDO)") (class "Default")
      (node (ref "D2") (pin "3") (pinfunction "SDO_3") (pintype "passive"))
      (node (ref "D3") (pin "4") (pinfunction "SDI_4") (pintype "passive"))
    )
    (net (code "15") (name "Net-(D3-CKO)") (class "Default")
      (node (ref "D3") (pin "2") (pinfunction "CKO_2") (pintype "passive"))
      (node (ref "D4") (pin "5") (pinfunction "CKI_5") (pintype "passive"))
    )
    (net (code "16") (name "Net-(D3-SDO)") (class "Default")
      (node (ref "D3") (pin "3") (pinfunction "SDO_3") (pintype "passive"))
      (node (ref "D4") (pin "4") (pinfunction "SDI_4") (pintype "passive"))
    )
    (net (code "17") (name "Net-(D4-CKO)") (class "Default")
      (node (ref "D4") (pin "2") (pinfunction "CKO_2") (pintype "passive"))
      (node (ref "D5") (pin "5") (pinfunction "CKI_5") (pintype "passive"))
    )
    (net (code "18") (name "Net-(D4-SDO)") (class "Default")
      (node (ref "D4") (pin "3") (pinfunction "SDO_3") (pintype "passive"))
      (node (ref "D5") (pin "4") (pinfunction "SDI_4") (pintype "passive"))
    )
    (net (code "19") (name "Net-(D5-CKO)") (class "Default")
      (node (ref "D5") (pin "2") (pinfunction "CKO_2") (pintype "passive"))
      (node (ref "D7") (pin "5") (pinfunction "CKI_5") (pintype "passive"))
    )
    (net (code "20") (name "Net-(D5-SDO)") (class "Default")
      (node (ref "D5") (pin "3") (pinfunction "SDO_3") (pintype "passive"))
      (node (ref "D7") (pin "4") (pinfunction "SDI_4") (pintype "passive"))
    )
    (net (code "21") (name "Net-(D6-CKI)") (class "Default")
      (node (ref "D6") (pin "5") (pinfunction "CKI_5") (pintype "passive"))
      (node (ref "D7") (pin "2") (pinfunction "CKO_2") (pintype "passive"))
    )
    (net (code "22") (name "Net-(D6-SDI)") (class "Default")
      (node (ref "D6") (pin "4") (pinfunction "SDI_4") (pintype "passive"))
      (node (ref "D7") (pin "3") (pinfunction "SDO_3") (pintype "passive"))
    )
    (net (code "23") (name "Net-(D8-CKI)") (class "Default")
      (node (ref "D8") (pin "5") (pinfunction "CKI_5") (pintype "passive"))
      (node (ref "D9") (pin "2") (pinfunction "CKO_2") (pintype "passive"))
    )
    (net (code "24") (name "Net-(D8-SDI)") (class "Default")
      (node (ref "D8") (pin "4") (pinfunction "SDI_4") (pintype "passive"))
      (node (ref "D9") (pin "3") (pinfunction "SDO_3") (pintype "passive"))
    )
    (net (code "25") (name "Net-(D10-CKI)") (class "Default")
      (node (ref "D10") (pin "5") (pinfunction "CKI_5") (pintype "passive"))
      (node (ref "D11") (pin "2") (pinfunction "CKO_2") (pintype "passive"))
    )
    (net (code "26") (name "Net-(D10-CKO)") (class "Default")
      (node (ref "D10") (pin "2") (pinfunction "CKO_2") (pintype "passive"))
      (node (ref "D9") (pin "5") (pinfunction "CKI_5") (pintype "passive"))
    )
    (net (code "27") (name "Net-(D10-SDI)") (class "Default")
      (node (ref "D10") (pin "4") (pinfunction "SDI_4") (pintype "passive"))
      (node (ref "D11") (pin "3") (pinfunction "SDO_3") (pintype "passive"))
    )
    (net (code "28") (name "Net-(D10-SDO)") (class "Default")
      (node (ref "D10") (pin "3") (pinfunction "SDO_3") (pintype "passive"))
      (node (ref "D9") (pin "4") (pinfunction "SDI_4") (pintype "passive"))
    )
    (net (code "29") (name "Net-(D11-CKI)") (class "Default")
      (node (ref "D11") (pin "5") (pinfunction "CKI_5") (pintype "passive"))
      (node (ref "D12") (pin "2") (pinfunction "CKO_2") (pintype "passive"))
    )
    (net (code "30") (name "Net-(D11-SDI)") (class "Default")
      (node (ref "D11") (pin "4") (pinfunction "SDI_4") (pintype "passive"))
      (node (ref "D12") (pin "3") (pinfunction "SDO_3") (pintype "passive"))
    )
    (net (code "31") (name "Net-(D12-CKI)") (class "Default")
      (node (ref "D12") (pin "5") (pinfunction "CKI_5") (pintype "passive"))
      (node (ref "D6") (pin "2") (pinfunction "CKO_2") (pintype "passive"))
    )
    (net (code "32") (name "Net-(D12-SDI)") (class "Default")
      (node (ref "D12") (pin "4") (pinfunction "SDI_4") (pintype "passive"))
      (node (ref "D6") (pin "3") (pinfunction "SDO_3") (pintype "passive"))
    )
    (net (code "33") (name "Net-(D13-CKI)") (class "Default")
      (node (ref "D13") (pin "5") (pinfunction "CKI_5") (pintype "passive"))
      (node (ref "D8") (pin "2") (pinfunction "CKO_2") (pintype "passive"))
    )
    (net (code "34") (name "Net-(D13-CKO)") (class "Default")
      (node (ref "D13") (pin "2") (pinfunction "CKO_2") (pintype "passive"))
      (node (ref "D14") (pin "5") (pinfunction "CKI_5") (pintype "passive"))
    )
    (net (code "35") (name "Net-(D13-SDI)") (class "Default")
      (node (ref "D13") (pin "4") (pinfunction "SDI_4") (pintype "passive"))
      (node (ref "D8") (pin "3") (pinfunction "SDO_3") (pintype "passive"))
    )
    (net (code "36") (name "Net-(D13-SDO)") (class "Default")
      (node (ref "D13") (pin "3") (pinfunction "SDO_3") (pintype "passive"))
      (node (ref "D14") (pin "4") (pinfunction "SDI_4") (pintype "passive"))
    )
    (net (code "37") (name "Net-(D14-CKO)") (class "Default")
      (node (ref "D14") (pin "2") (pinfunction "CKO_2") (pintype "passive"))
      (node (ref "D17") (pin "5") (pinfunction "CKI_5") (pintype "passive"))
    )
    (net (code "38") (name "Net-(D14-SDO)") (class "Default")
      (node (ref "D14") (pin "3") (pinfunction "SDO_3") (pintype "passive"))
      (node (ref "D17") (pin "4") (pinfunction "SDI_4") (pintype "passive"))
    )
    (net (code "39") (name "Net-(D15-CKI)") (class "Default")
      (node (ref "D15") (pin "5") (pinfunction "CKI_5") (pintype "passive"))
      (node (ref "D17") (pin "2") (pinfunction "CKO_2") (pintype "passive"))
    )
    (net (code "40") (name "Net-(D15-CKO)") (class "Default")
      (node (ref "D15") (pin "2") (pinfunction "CKO_2") (pintype "passive"))
      (node (ref "D16") (pin "5") (pinfunction "CKI_5") (pintype "passive"))
    )
    (net (code "41") (name "Net-(D15-SDI)") (class "Default")
      (node (ref "D15") (pin "4") (pinfunction "SDI_4") (pintype "passive"))
      (node (ref "D17") (pin "3") (pinfunction "SDO_3") (pintype "passive"))
    )
    (net (code "42") (name "Net-(D15-SDO)") (class "Default")
      (node (ref "D15") (pin "3") (pinfunction "SDO_3") (pintype "passive"))
      (node (ref "D16") (pin "4") (pinfunction "SDI_4") (pintype "passive"))
    )
    (net (code "43") (name "Net-(D16-CKO)") (class "Default")
      (node (ref "D16") (pin "2") (pinfunction "CKO_2") (pintype "passive"))
      (node (ref "D18") (pin "5") (pinfunction "CKI_5") (pintype "passive"))
    )
    (net (code "44") (name "Net-(D16-SDO)") (class "Default")
      (node (ref "D16") (pin "3") (pinfunction "SDO_3") (pintype "passive"))
      (node (ref "D18") (pin "4") (pinfunction "SDI_4") (pintype "passive"))
    )
    (net (code "45") (name "Net-(D18-CKO)") (class "Default")
      (node (ref "D18") (pin "2") (pinfunction "CKO_2") (pintype "passive"))
      (node (ref "D19") (pin "5") (pinfunction "CKI_5") (pintype "passive"))
    )
    (net (code "46") (name "Net-(D18-SDO)") (class "Default")
      (node (ref "D18") (pin "3") (pinfunction "SDO_3") (pintype "passive"))
      (node (ref "D19") (pin "4") (pinfunction "SDI_4") (pintype "passive"))
    )
    (net (code "47") (name "Net-(D19-CKO)") (class "Default")
      (node (ref "D19") (pin "2") (pinfunction "CKO_2") (pintype "passive"))
      (node (ref "D20") (pin "5") (pinfunction "CKI_5") (pintype "passive"))
    )
    (net (code "48") (name "Net-(D19-SDO)") (class "Default")
      (node (ref "D19") (pin "3") (pinfunction "SDO_3") (pintype "passive"))
      (node (ref "D20") (pin "4") (pinfunction "SDI_4") (pintype "passive"))
    )
    (net (code "49") (name "Net-(D20-CKO)") (class "Default")
      (node (ref "D20") (pin "2") (pinfunction "CKO_2") (pintype "passive"))
      (node (ref "D21") (pin "5") (pinfunction "CKI_5") (pintype "passive"))
    )
    (net (code "50") (name "Net-(D20-SDO)") (class "Default")
      (node (ref "D20") (pin "3") (pinfunction "SDO_3") (pintype "passive"))
      (node (ref "D21") (pin "4") (pinfunction "SDI_4") (pintype "passive"))
    )
    (net (code "51") (name "Net-(D21-CKO)") (class "Default")
      (node (ref "D21") (pin "2") (pinfunction "CKO_2") (pintype "passive"))
      (node (ref "D25") (pin "5") (pinfunction "CKI_5") (pintype "passive"))
    )
    (net (code "52") (name "Net-(D21-SDO)") (class "Default")
      (node (ref "D21") (pin "3") (pinfunction "SDO_3") (pintype "passive"))
      (node (ref "D25") (pin "4") (pinfunction "SDI_4") (pintype "passive"))
    )
    (net (code "53") (name "Net-(D22-CKI)") (class "Default")
      (node (ref "D22") (pin "5") (pinfunction "CKI_5") (pintype "passive"))
      (node (ref "D23") (pin "2") (pinfunction "CKO_2") (pintype "passive"))
    )
    (net (code "54") (name "Net-(D22-CKO)") (class "Default")
      (node (ref "D22") (pin "2") (pinfunction "CKO_2") (pintype "passive"))
      (node (ref "D26") (pin "5") (pinfunction "CKI_5") (pintype "passive"))
    )
    (net (code "55") (name "Net-(D22-SDI)") (class "Default")
      (node (ref "D22") (pin "4") (pinfunction "SDI_4") (pintype "passive"))
      (node (ref "D23") (pin "3") (pinfunction "SDO_3") (pintype "passive"))
    )
    (net (code "56") (name "Net-(D22-SDO)") (class "Default")
      (node (ref "D22") (pin "3") (pinfunction "SDO_3") (pintype "passive"))
      (node (ref "D26") (pin "4") (pinfunction "SDI_4") (pintype "passive"))
    )
    (net (code "57") (name "Net-(D23-CKI)") (class "Default")
      (node (ref "D23") (pin "5") (pinfunction "CKI_5") (pintype "passive"))
      (node (ref "D24") (pin "2") (pinfunction "CKO_2") (pintype "passive"))
    )
    (net (code "58") (name "Net-(D23-SDI)") (class "Default")
      (node (ref "D23") (pin "4") (pinfunction "SDI_4") (pintype "passive"))
      (node (ref "D24") (pin "3") (pinfunction "SDO_3") (pintype "passive"))
    )
    (net (code "59") (name "Net-(D24-CKI)") (class "Default")
      (node (ref "D24") (pin "5") (pinfunction "CKI_5") (pintype "passive"))
      (node (ref "D25") (pin "2") (pinfunction "CKO_2") (pintype "passive"))
    )
    (net (code "60") (name "Net-(D24-SDI)") (class "Default")
      (node (ref "D24") (pin "4") (pinfunction "SDI_4") (pintype "passive"))
      (node (ref "D25") (pin "3") (pinfunction "SDO_3") (pintype "passive"))
    )
    (net (code "61") (name "Net-(D26-CKO)") (class "Default")
      (node (ref "D26") (pin "2") (pinfunction "CKO_2") (pintype "passive"))
      (node (ref "D27") (pin "5") (pinfunction "CKI_5") (pintype "passive"))
    )
    (net (code "62") (name "Net-(D26-SDO)") (class "Default")
      (node (ref "D26") (pin "3") (pinfunction "SDO_3") (pintype "passive"))
      (node (ref "D27") (pin "4") (pinfunction "SDI_4") (pintype "passive"))
    )
    (net (code "63") (name "Net-(D27-CKO)") (class "Default")
      (node (ref "D27") (pin "2") (pinfunction "CKO_2") (pintype "passive"))
      (node (ref "D28") (pin "5") (pinfunction "CKI_5") (pintype "passive"))
    )
    (net (code "64") (name "Net-(D27-SDO)") (class "Default")
      (node (ref "D27") (pin "3") (pinfunction "SDO_3") (pintype "passive"))
      (node (ref "D28") (pin "4") (pinfunction "SDI_4") (pintype "passive"))
    )
    (net (code "65") (name "Net-(D28-CKO)") (class "Default")
      (node (ref "D28") (pin "2") (pinfunction "CKO_2") (pintype "passive"))
      (node (ref "D29") (pin "5") (pinfunction "CKI_5") (pintype "passive"))
    )
    (net (code "66") (name "Net-(D28-SDO)") (class "Default")
      (node (ref "D28") (pin "3") (pinfunction "SDO_3") (pintype "passive"))
      (node (ref "D29") (pin "4") (pinfunction "SDI_4") (pintype "passive"))
    )
    (net (code "67") (name "Net-(D29-CKO)") (class "Default")
      (node (ref "D29") (pin "2") (pinfunction "CKO_2") (pintype "passive"))
      (node (ref "D30") (pin "5") (pinfunction "CKI_5") (pintype "passive"))
    )
    (net (code "68") (name "Net-(D29-SDO)") (class "Default")
      (node (ref "D29") (pin "3") (pinfunction "SDO_3") (pintype "passive"))
      (node (ref "D30") (pin "4") (pinfunction "SDI_4") (pintype "passive"))
    )
    (net (code "69") (name "Net-(D30-CKO)") (class "Default")
      (node (ref "D30") (pin "2") (pinfunction "CKO_2") (pintype "passive"))
      (node (ref "D31") (pin "5") (pinfunction "CKI_5") (pintype "passive"))
    )
    (net (code "70") (name "Net-(D30-SDO)") (class "Default")
      (node (ref "D30") (pin "3") (pinfunction "SDO_3") (pintype "passive"))
      (node (ref "D31") (pin "4") (pinfunction "SDI_4") (pintype "passive"))
    )
    (net (code "71") (name "Net-(D31-CKO)") (class "Default")
      (node (ref "D31") (pin "2") (pinfunction "CKO_2") (pintype "passive"))
      (node (ref "D32") (pin "5") (pinfunction "CKI_5") (pintype "passive"))
    )
    (net (code "72") (name "Net-(D31-SDO)") (class "Default")
      (node (ref "D31") (pin "3") (pinfunction "SDO_3") (pintype "passive"))
      (node (ref "D32") (pin "4") (pinfunction "SDI_4") (pintype "passive"))
    )
    (net (code "73") (name "Net-(D32-CKO)") (class "Default")
      (node (ref "D32") (pin "2") (pinfunction "CKO_2") (pintype "passive"))
      (node (ref "D33") (pin "5") (pinfunction "CKI_5") (pintype "passive"))
    )
    (net (code "74") (name "Net-(D32-SDO)") (class "Default")
      (node (ref "D32") (pin "3") (pinfunction "SDO_3") (pintype "passive"))
      (node (ref "D33") (pin "4") (pinfunction "SDI_4") (pintype "passive"))
    )
    (net (code "75") (name "Net-(D33-CKO)") (class "Default")
      (node (ref "D33") (pin "2") (pinfunction "CKO_2") (pintype "passive"))
      (node (ref "D34") (pin "5") (pinfunction "CKI_5") (pintype "passive"))
    )
    (net (code "76") (name "Net-(D33-SDO)") (class "Default")
      (node (ref "D33") (pin "3") (pinfunction "SDO_3") (pintype "passive"))
      (node (ref "D34") (pin "4") (pinfunction "SDI_4") (pintype "passive"))
    )
    (net (code "77") (name "Net-(D34-CKO)") (class "Default")
      (node (ref "D34") (pin "2") (pinfunction "CKO_2") (pintype "passive"))
      (node (ref "D35") (pin "5") (pinfunction "CKI_5") (pintype "passive"))
    )
    (net (code "78") (name "Net-(D34-SDO)") (class "Default")
      (node (ref "D34") (pin "3") (pinfunction "SDO_3") (pintype "passive"))
      (node (ref "D35") (pin "4") (pinfunction "SDI_4") (pintype "passive"))
    )
    (net (code "79") (name "Net-(D35-CKO)") (class "Default")
      (node (ref "D35") (pin "2") (pinfunction "CKO_2") (pintype "passive"))
      (node (ref "D36") (pin "5") (pinfunction "CKI_5") (pintype "passive"))
    )
    (net (code "80") (name "Net-(D35-SDO)") (class "Default")
      (node (ref "D35") (pin "3") (pinfunction "SDO_3") (pintype "passive"))
      (node (ref "D36") (pin "4") (pinfunction "SDI_4") (pintype "passive"))
    )
    (net (code "81") (name "Net-(D36-CKO)") (class "Default")
      (node (ref "D36") (pin "2") (pinfunction "CKO_2") (pintype "passive"))
      (node (ref "D37") (pin "5") (pinfunction "CKI_5") (pintype "passive"))
    )
    (net (code "82") (name "Net-(D36-SDO)") (class "Default")
      (node (ref "D36") (pin "3") (pinfunction "SDO_3") (pintype "passive"))
      (node (ref "D37") (pin "4") (pinfunction "SDI_4") (pintype "passive"))
    )
    (net (code "83") (name "Net-(D37-CKO)") (class "Default")
      (node (ref "D37") (pin "2") (pinfunction "CKO_2") (pintype "passive"))
      (node (ref "D38") (pin "5") (pinfunction "CKI_5") (pintype "passive"))
    )
    (net (code "84") (name "Net-(D37-SDO)") (class "Default")
      (node (ref "D37") (pin "3") (pinfunction "SDO_3") (pintype "passive"))
      (node (ref "D38") (pin "4") (pinfunction "SDI_4") (pintype "passive"))
    )
    (net (code "85") (name "Net-(D38-CKO)") (class "Default")
      (node (ref "D38") (pin "2") (pinfunction "CKO_2") (pintype "passive"))
      (node (ref "D39") (pin "5") (pinfunction "CKI_5") (pintype "passive"))
    )
    (net (code "86") (name "Net-(D38-SDO)") (class "Default")
      (node (ref "D38") (pin "3") (pinfunction "SDO_3") (pintype "passive"))
      (node (ref "D39") (pin "4") (pinfunction "SDI_4") (pintype "passive"))
    )
    (net (code "87") (name "Net-(D39-CKO)") (class "Default")
      (node (ref "D39") (pin "2") (pinfunction "CKO_2") (pintype "passive"))
      (node (ref "D45") (pin "5") (pinfunction "CKI_5") (pintype "passive"))
    )
    (net (code "88") (name "Net-(D39-SDO)") (class "Default")
      (node (ref "D39") (pin "3") (pinfunction "SDO_3") (pintype "passive"))
      (node (ref "D45") (pin "4") (pinfunction "SDI_4") (pintype "passive"))
    )
    (net (code "89") (name "Net-(D40-CKI)") (class "Default")
      (node (ref "D40") (pin "5") (pinfunction "CKI_5") (pintype "passive"))
      (node (ref "D41") (pin "2") (pinfunction "CKO_2") (pintype "passive"))
    )
    (net (code "90") (name "Net-(D40-CKO)") (class "Default")
      (node (ref "D40") (pin "2") (pinfunction "CKO_2") (pintype "passive"))
      (node (ref "D46") (pin "5") (pinfunction "CKI_5") (pintype "passive"))
    )
    (net (code "91") (name "Net-(D40-SDI)") (class "Default")
      (node (ref "D40") (pin "4") (pinfunction "SDI_4") (pintype "passive"))
      (node (ref "D41") (pin "3") (pinfunction "SDO_3") (pintype "passive"))
    )
    (net (code "92") (name "Net-(D40-SDO)") (class "Default")
      (node (ref "D40") (pin "3") (pinfunction "SDO_3") (pintype "passive"))
      (node (ref "D46") (pin "4") (pinfunction "SDI_4") (pintype "passive"))
    )
    (net (code "93") (name "Net-(D41-CKI)") (class "Default")
      (node (ref "D41") (pin "5") (pinfunction "CKI_5") (pintype "passive"))
      (node (ref "D42") (pin "2") (pinfunction "CKO_2") (pintype "passive"))
    )
    (net (code "94") (name "Net-(D41-SDI)") (class "Default")
      (node (ref "D41") (pin "4") (pinfunction "SDI_4") (pintype "passive"))
      (node (ref "D42") (pin "3") (pinfunction "SDO_3") (pintype "passive"))
    )
    (net (code "95") (name "Net-(D42-CKI)") (class "Default")
      (node (ref "D42") (pin "5") (pinfunction "CKI_5") (pintype "passive"))
      (node (ref "D43") (pin "2") (pinfunction "CKO_2") (pintype "passive"))
    )
    (net (code "96") (name "Net-(D42-SDI)") (class "Default")
      (node (ref "D42") (pin "4") (pinfunction "SDI_4") (pintype "passive"))
      (node (ref "D43") (pin "3") (pinfunction "SDO_3") (pintype "passive"))
    )
    (net (code "97") (name "Net-(D43-CKI)") (class "Default")
      (node (ref "D43") (pin "5") (pinfunction "CKI_5") (pintype "passive"))
      (node (ref "D44") (pin "2") (pinfunction "CKO_2") (pintype "passive"))
    )
    (net (code "98") (name "Net-(D43-SDI)") (class "Default")
      (node (ref "D43") (pin "4") (pinfunction "SDI_4") (pintype "passive"))
      (node (ref "D44") (pin "3") (pinfunction "SDO_3") (pintype "passive"))
    )
    (net (code "99") (name "Net-(D44-CKI)") (class "Default")
      (node (ref "D44") (pin "5") (pinfunction "CKI_5") (pintype "passive"))
      (node (ref "D45") (pin "2") (pinfunction "CKO_2") (pintype "passive"))
    )
    (net (code "100") (name "Net-(D44-SDI)") (class "Default")
      (node (ref "D44") (pin "4") (pinfunction "SDI_4") (pintype "passive"))
      (node (ref "D45") (pin "3") (pinfunction "SDO_3") (pintype "passive"))
    )
    (net (code "101") (name "Net-(D46-CKO)") (class "Default")
      (node (ref "D46") (pin "2") (pinfunction "CKO_2") (pintype "passive"))
      (node (ref "D47") (pin "5") (pinfunction "CKI_5") (pintype "passive"))
    )
    (net (code "102") (name "Net-(D46-SDO)") (class "Default")
      (node (ref "D46") (pin "3") (pinfunction "SDO_3") (pintype "passive"))
      (node (ref "D47") (pin "4") (pinfunction "SDI_4") (pintype "passive"))
    )
    (net (code "103") (name "Net-(D47-CKO)") (class "Default")
      (node (ref "D47") (pin "2") (pinfunction "CKO_2") (pintype "passive"))
      (node (ref "D51") (pin "5") (pinfunction "CKI_5") (pintype "passive"))
    )
    (net (code "104") (name "Net-(D47-SDO)") (class "Default")
      (node (ref "D47") (pin "3") (pinfunction "SDO_3") (pintype "passive"))
      (node (ref "D51") (pin "4") (pinfunction "SDI_4") (pintype "passive"))
    )
    (net (code "105") (name "Net-(D48-CKI)") (class "Default")
      (node (ref "D48") (pin "5") (pinfunction "CKI_5") (pintype "passive"))
      (node (ref "D49") (pin "2") (pinfunction "CKO_2") (pintype "passive"))
    )
    (net (code "106") (name "Net-(D48-CKO)") (class "Default")
      (node (ref "D48") (pin "2") (pinfunction "CKO_2") (pintype "passive"))
      (node (ref "D52") (pin "5") (pinfunction "CKI_5") (pintype "passive"))
    )
    (net (code "107") (name "Net-(D48-SDI)") (class "Default")
      (node (ref "D48") (pin "4") (pinfunction "SDI_4") (pintype "passive"))
      (node (ref "D49") (pin "3") (pinfunction "SDO_3") (pintype "passive"))
    )
    (net (code "108") (name "Net-(D48-SDO)") (class "Default")
      (node (ref "D48") (pin "3") (pinfunction "SDO_3") (pintype "passive"))
      (node (ref "D52") (pin "4") (pinfunction "SDI_4") (pintype "passive"))
    )
    (net (code "109") (name "Net-(D49-CKI)") (class "Default")
      (node (ref "D49") (pin "5") (pinfunction "CKI_5") (pintype "passive"))
      (node (ref "D50") (pin "2") (pinfunction "CKO_2") (pintype "passive"))
    )
    (net (code "110") (name "Net-(D49-SDI)") (class "Default")
      (node (ref "D49") (pin "4") (pinfunction "SDI_4") (pintype "passive"))
      (node (ref "D50") (pin "3") (pinfunction "SDO_3") (pintype "passive"))
    )
    (net (code "111") (name "Net-(D50-CKI)") (class "Default")
      (node (ref "D50") (pin "5") (pinfunction "CKI_5") (pintype "passive"))
      (node (ref "D51") (pin "2") (pinfunction "CKO_2") (pintype "passive"))
    )
    (net (code "112") (name "Net-(D50-SDI)") (class "Default")
      (node (ref "D50") (pin "4") (pinfunction "SDI_4") (pintype "passive"))
      (node (ref "D51") (pin "3") (pinfunction "SDO_3") (pintype "passive"))
    )
    (net (code "113") (name "Net-(D52-CKO)") (class "Default")
      (node (ref "D52") (pin "2") (pinfunction "CKO_2") (pintype "passive"))
      (node (ref "D53") (pin "5") (pinfunction "CKI_5") (pintype "passive"))
    )
    (net (code "114") (name "Net-(D52-SDO)") (class "Default")
      (node (ref "D52") (pin "3") (pinfunction "SDO_3") (pintype "passive"))
      (node (ref "D53") (pin "4") (pinfunction "SDI_4") (pintype "passive"))
    )
    (net (code "115") (name "Net-(D53-CKO)") (class "Default")
      (node (ref "D53") (pin "2") (pinfunction "CKO_2") (pintype "passive"))
      (node (ref "D54") (pin "5") (pinfunction "CKI_5") (pintype "passive"))
    )
    (net (code "116") (name "Net-(D53-SDO)") (class "Default")
      (node (ref "D53") (pin "3") (pinfunction "SDO_3") (pintype "passive"))
      (node (ref "D54") (pin "4") (pinfunction "SDI_4") (pintype "passive"))
    )
    (net (code "117") (name "Net-(D54-CKO)") (class "Default")
      (node (ref "D54") (pin "2") (pinfunction "CKO_2") (pintype "passive"))
      (node (ref "D55") (pin "5") (pinfunction "CKI_5") (pintype "passive"))
    )
    (net (code "118") (name "Net-(D54-SDO)") (class "Default")
      (node (ref "D54") (pin "3") (pinfunction "SDO_3") (pintype "passive"))
      (node (ref "D55") (pin "4") (pinfunction "SDI_4") (pintype "passive"))
    )
    (net (code "119") (name "Net-(D55-CKO)") (class "Default")
      (node (ref "D55") (pin "2") (pinfunction "CKO_2") (pintype "passive"))
      (node (ref "D56") (pin "5") (pinfunction "CKI_5") (pintype "passive"))
    )
    (net (code "120") (name "Net-(D55-SDO)") (class "Default")
      (node (ref "D55") (pin "3") (pinfunction "SDO_3") (pintype "passive"))
      (node (ref "D56") (pin "4") (pinfunction "SDI_4") (pintype "passive"))
    )
    (net (code "121") (name "Net-(D56-CKO)") (class "Default")
      (node (ref "D56") (pin "2") (pinfunction "CKO_2") (pintype "passive"))
      (node (ref "D57") (pin "5") (pinfunction "CKI_5") (pintype "passive"))
    )
    (net (code "122") (name "Net-(D56-SDO)") (class "Default")
      (node (ref "D56") (pin "3") (pinfunction "SDO_3") (pintype "passive"))
      (node (ref "D57") (pin "4") (pinfunction "SDI_4") (pintype "passive"))
    )
    (net (code "123") (name "Net-(D57-CKO)") (class "Default")
      (node (ref "D57") (pin "2") (pinfunction "CKO_2") (pintype "passive"))
      (node (ref "D58") (pin "5") (pinfunction "CKI_5") (pintype "passive"))
    )
    (net (code "124") (name "Net-(D57-SDO)") (class "Default")
      (node (ref "D57") (pin "3") (pinfunction "SDO_3") (pintype "passive"))
      (node (ref "D58") (pin "4") (pinfunction "SDI_4") (pintype "passive"))
    )
    (net (code "125") (name "Net-(D58-CKO)") (class "Default")
      (node (ref "D58") (pin "2") (pinfunction "CKO_2") (pintype "passive"))
      (node (ref "D59") (pin "5") (pinfunction "CKI_5") (pintype "passive"))
    )
    (net (code "126") (name "Net-(D58-SDO)") (class "Default")
      (node (ref "D58") (pin "3") (pinfunction "SDO_3") (pintype "passive"))
      (node (ref "D59") (pin "4") (pinfunction "SDI_4") (pintype "passive"))
    )
    (net (code "127") (name "Net-(D59-CKO)") (class "Default")
      (node (ref "D59") (pin "2") (pinfunction "CKO_2") (pintype "passive"))
      (node (ref "D60") (pin "5") (pinfunction "CKI_5") (pintype "passive"))
    )
    (net (code "128") (name "Net-(D59-SDO)") (class "Default")
      (node (ref "D59") (pin "3") (pinfunction "SDO_3") (pintype "passive"))
      (node (ref "D60") (pin "4") (pinfunction "SDI_4") (pintype "passive"))
    )
    (net (code "129") (name "Net-(D60-CKO)") (class "Default")
      (node (ref "D60") (pin "2") (pinfunction "CKO_2") (pintype "passive"))
      (node (ref "D61") (pin "5") (pinfunction "CKI_5") (pintype "passive"))
    )
    (net (code "130") (name "Net-(D60-SDO)") (class "Default")
      (node (ref "D60") (pin "3") (pinfunction "SDO_3") (pintype "passive"))
      (node (ref "D61") (pin "4") (pinfunction "SDI_4") (pintype "passive"))
    )
    (net (code "131") (name "Net-(D61-CKO)") (class "Default")
      (node (ref "D61") (pin "2") (pinfunction "CKO_2") (pintype "passive"))
      (node (ref "D62") (pin "5") (pinfunction "CKI_5") (pintype "passive"))
    )
    (net (code "132") (name "Net-(D61-SDO)") (class "Default")
      (node (ref "D61") (pin "3") (pinfunction "SDO_3") (pintype "passive"))
      (node (ref "D62") (pin "4") (pinfunction "SDI_4") (pintype "passive"))
    )
    (net (code "133") (name "Net-(D62-CKO)") (class "Default")
      (node (ref "D62") (pin "2") (pinfunction "CKO_2") (pintype "passive"))
      (node (ref "D63") (pin "5") (pinfunction "CKI_5") (pintype "passive"))
    )
    (net (code "134") (name "Net-(D62-SDO)") (class "Default")
      (node (ref "D62") (pin "3") (pinfunction "SDO_3") (pintype "passive"))
      (node (ref "D63") (pin "4") (pinfunction "SDI_4") (pintype "passive"))
    )
    (net (code "135") (name "Net-(D63-CKO)") (class "Default")
      (node (ref "D63") (pin "2") (pinfunction "CKO_2") (pintype "passive"))
      (node (ref "D64") (pin "5") (pinfunction "CKI_5") (pintype "passive"))
    )
    (net (code "136") (name "Net-(D63-SDO)") (class "Default")
      (node (ref "D63") (pin "3") (pinfunction "SDO_3") (pintype "passive"))
      (node (ref "D64") (pin "4") (pinfunction "SDI_4") (pintype "passive"))
    )
    (net (code "137") (name "Net-(D64-CKO)") (class "Default")
      (node (ref "D64") (pin "2") (pinfunction "CKO_2") (pintype "passive"))
      (node (ref "D65") (pin "5") (pinfunction "CKI_5") (pintype "passive"))
    )
    (net (code "138") (name "Net-(D64-SDO)") (class "Default")
      (node (ref "D64") (pin "3") (pinfunction "SDO_3") (pintype "passive"))
      (node (ref "D65") (pin "4") (pinfunction "SDI_4") (pintype "passive"))
    )
    (net (code "139") (name "Net-(D65-CKO)") (class "Default")
      (node (ref "D65") (pin "2") (pinfunction "CKO_2") (pintype "passive"))
      (node (ref "D66") (pin "5") (pinfunction "CKI_5") (pintype "passive"))
    )
    (net (code "140") (name "Net-(D65-SDO)") (class "Default")
      (node (ref "D65") (pin "3") (pinfunction "SDO_3") (pintype "passive"))
      (node (ref "D66") (pin "4") (pinfunction "SDI_4") (pintype "passive"))
    )
    (net (code "141") (name "Net-(D66-CKO)") (class "Default")
      (node (ref "D66") (pin "2") (pinfunction "CKO_2") (pintype "passive"))
      (node (ref "D67") (pin "5") (pinfunction "CKI_5") (pintype "passive"))
    )
    (net (code "142") (name "Net-(D66-SDO)") (class "Default")
      (node (ref "D66") (pin "3") (pinfunction "SDO_3") (pintype "passive"))
      (node (ref "D67") (pin "4") (pinfunction "SDI_4") (pintype "passive"))
    )
    (net (code "143") (name "Net-(D67-CKO)") (class "Default")
      (node (ref "D67") (pin "2") (pinfunction "CKO_2") (pintype "passive"))
      (node (ref "D68") (pin "5") (pinfunction "CKI_5") (pintype "passive"))
    )
    (net (code "144") (name "Net-(D67-SDO)") (class "Default")
      (node (ref "D67") (pin "3") (pinfunction "SDO_3") (pintype "passive"))
      (node (ref "D68") (pin "4") (pinfunction "SDI_4") (pintype "passive"))
    )
    (net (code "145") (name "Net-(D68-CKO)") (class "Default")
      (node (ref "D68") (pin "2") (pinfunction "CKO_2") (pintype "passive"))
      (node (ref "D69") (pin "5") (pinfunction "CKI_5") (pintype "passive"))
    )
    (net (code "146") (name "Net-(D68-SDO)") (class "Default")
      (node (ref "D68") (pin "3") (pinfunction "SDO_3") (pintype "passive"))
      (node (ref "D69") (pin "4") (pinfunction "SDI_4") (pintype "passive"))
    )
    (net (code "147") (name "Net-(D69-CKO)") (class "Default")
      (node (ref "D69") (pin "2") (pinfunction "CKO_2") (pintype "passive"))
      (node (ref "D70") (pin "5") (pinfunction "CKI_5") (pintype "passive"))
    )
    (net (code "148") (name "Net-(D69-SDO)") (class "Default")
      (node (ref "D69") (pin "3") (pinfunction "SDO_3") (pintype "passive"))
      (node (ref "D70") (pin "4") (pinfunction "SDI_4") (pintype "passive"))
    )
    (net (code "149") (name "Net-(D70-CKO)") (class "Default")
      (node (ref "D70") (pin "2") (pinfunction "CKO_2") (pintype "passive"))
      (node (ref "D71") (pin "5") (pinfunction "CKI_5") (pintype "passive"))
    )
    (net (code "150") (name "Net-(D70-SDO)") (class "Default")
      (node (ref "D70") (pin "3") (pinfunction "SDO_3") (pintype "passive"))
      (node (ref "D71") (pin "4") (pinfunction "SDI_4") (pintype "passive"))
    )
    (net (code "151") (name "Net-(D71-CKO)") (class "Default")
      (node (ref "D71") (pin "2") (pinfunction "CKO_2") (pintype "passive"))
      (node (ref "D72") (pin "5") (pinfunction "CKI_5") (pintype "passive"))
    )
    (net (code "152") (name "Net-(D71-SDO)") (class "Default")
      (node (ref "D71") (pin "3") (pinfunction "SDO_3") (pintype "passive"))
      (node (ref "D72") (pin "4") (pinfunction "SDI_4") (pintype "passive"))
    )
    (net (code "153") (name "Net-(D72-CKO)") (class "Default")
      (node (ref "D72") (pin "2") (pinfunction "CKO_2") (pintype "passive"))
      (node (ref "D73") (pin "5") (pinfunction "CKI_5") (pintype "passive"))
    )
    (net (code "154") (name "Net-(D72-SDO)") (class "Default")
      (node (ref "D72") (pin "3") (pinfunction "SDO_3") (pintype "passive"))
      (node (ref "D73") (pin "4") (pinfunction "SDI_4") (pintype "passive"))
    )
    (net (code "155") (name "Net-(D73-CKO)") (class "Default")
      (node (ref "D73") (pin "2") (pinfunction "CKO_2") (pintype "passive"))
      (node (ref "D74") (pin "5") (pinfunction "CKI_5") (pintype "passive"))
    )
    (net (code "156") (name "Net-(D73-SDO)") (class "Default")
      (node (ref "D73") (pin "3") (pinfunction "SDO_3") (pintype "passive"))
      (node (ref "D74") (pin "4") (pinfunction "SDI_4") (pintype "passive"))
    )
    (net (code "157") (name "Net-(D74-CKO)") (class "Default")
      (node (ref "D74") (pin "2") (pinfunction "CKO_2") (pintype "passive"))
      (node (ref "D75") (pin "5") (pinfunction "CKI_5") (pintype "passive"))
    )
    (net (code "158") (name "Net-(D74-SDO)") (class "Default")
      (node (ref "D74") (pin "3") (pinfunction "SDO_3") (pintype "passive"))
      (node (ref "D75") (pin "4") (pinfunction "SDI_4") (pintype "passive"))
    )
    (net (code "159") (name "Net-(D75-CKO)") (class "Default")
      (node (ref "D75") (pin "2") (pinfunction "CKO_2") (pintype "passive"))
      (node (ref "D76") (pin "5") (pinfunction "CKI_5") (pintype "passive"))
    )
    (net (code "160") (name "Net-(D75-SDO)") (class "Default")
      (node (ref "D75") (pin "3") (pinfunction "SDO_3") (pintype "passive"))
      (node (ref "D76") (pin "4") (pinfunction "SDI_4") (pintype "passive"))
    )
    (net (code "161") (name "Net-(D76-CKO)") (class "Default")
      (node (ref "D76") (pin "2") (pinfunction "CKO_2") (pintype "passive"))
      (node (ref "D81") (pin "5") (pinfunction "CKI_5") (pintype "passive"))
    )
    (net (code "162") (name "Net-(D76-SDO)") (class "Default")
      (node (ref "D76") (pin "3") (pinfunction "SDO_3") (pintype "passive"))
      (node (ref "D81") (pin "4") (pinfunction "SDI_4") (pintype "passive"))
    )
    (net (code "163") (name "Net-(D77-CKI)") (class "Default")
      (node (ref "D77") (pin "5") (pinfunction "CKI_5") (pintype "passive"))
      (node (ref "D78") (pin "2") (pinfunction "CKO_2") (pintype "passive"))
    )
    (net (code "164") (name "Net-(D77-CKO)") (class "Default")
      (node (ref "D77") (pin "2") (pinfunction "CKO_2") (pintype "passive"))
      (node (ref "D82") (pin "5") (pinfunction "CKI_5") (pintype "passive"))
    )
    (net (code "165") (name "Net-(D77-SDI)") (class "Default")
      (node (ref "D77") (pin "4") (pinfunction "SDI_4") (pintype "passive"))
      (node (ref "D78") (pin "3") (pinfunction "SDO_3") (pintype "passive"))
    )
    (net (code "166") (name "Net-(D77-SDO)") (class "Default")
      (node (ref "D77") (pin "3") (pinfunction "SDO_3") (pintype "passive"))
      (node (ref "D82") (pin "4") (pinfunction "SDI_4") (pintype "passive"))
    )
    (net (code "167") (name "Net-(D78-CKI)") (class "Default")
      (node (ref "D78") (pin "5") (pinfunction "CKI_5") (pintype "passive"))
      (node (ref "D79") (pin "2") (pinfunction "CKO_2") (pintype "passive"))
    )
    (net (code "168") (name "Net-(D78-SDI)") (class "Default")
      (node (ref "D78") (pin "4") (pinfunction "SDI_4") (pintype "passive"))
      (node (ref "D79") (pin "3") (pinfunction "SDO_3") (pintype "passive"))
    )
    (net (code "169") (name "Net-(D79-CKI)") (class "Default")
      (node (ref "D79") (pin "5") (pinfunction "CKI_5") (pintype "passive"))
      (node (ref "D80") (pin "2") (pinfunction "CKO_2") (pintype "passive"))
    )
    (net (code "170") (name "Net-(D79-SDI)") (class "Default")
      (node (ref "D79") (pin "4") (pinfunction "SDI_4") (pintype "passive"))
      (node (ref "D80") (pin "3") (pinfunction "SDO_3") (pintype "passive"))
    )
    (net (code "171") (name "Net-(D80-CKI)") (class "Default")
      (node (ref "D80") (pin "5") (pinfunction "CKI_5") (pintype "passive"))
      (node (ref "D81") (pin "2") (pinfunction "CKO_2") (pintype "passive"))
    )
    (net (code "172") (name "Net-(D80-SDI)") (class "Default")
      (node (ref "D80") (pin "4") (pinfunction "SDI_4") (pintype "passive"))
      (node (ref "D81") (pin "3") (pinfunction "SDO_3") (pintype "passive"))
    )
    (net (code "173") (name "Net-(J2-VBUS)") (class "Default")
      (node (ref "J2") (pin "1") (pinfunction "VBUS_1") (pintype "power_in"))
      (node (ref "P1") (pin "1") (pinfunction "1_1") (pintype "passive"))
      (node (ref "SW1") (pin "2") (pinfunction "COM_2") (pintype "passive"))
    )
    (net (code "174") (name "Net-(U1-PD5{slash}SYNC{slash}OC1B{slash}XCK1{slash}MOSI)") (class "Default")
      (node (ref "U1") (pin "25") (pinfunction "PD5/SYNC/OC1B/XCK1/MOSI_25") (pintype "bidirectional"))
      (node (ref "U2") (pin "5") (pinfunction "A1_5") (pintype "bidirectional"))
    )
    (net (code "175") (name "Net-(U1-PD7{slash}SYNC{slash}D+{slash}TXD1{slash}SCK{slash}CLKPER{slash}EVOUT)") (class "Default")
      (node (ref "U1") (pin "27") (pinfunction "PD7/SYNC/D+/TXD1/SCK/CLKPER/EVOUT_27") (pintype "bidirectional"))
      (node (ref "U2") (pin "4") (pinfunction "A2_4") (pintype "bidirectional"))
    )
    (net (code "176") (name "VCC_P3V3") (class "Default")
      (node (ref "C1") (pin "2") (pinfunction "2_2") (pintype "passive"))
      (node (ref "C10") (pin "2") (pinfunction "2_2") (pintype "passive"))
      (node (ref "C2") (pin "2") (pinfunction "2_2") (pintype "passive"))
      (node (ref "C3") (pin "2") (pinfunction "2_2") (pintype "passive"))
      (node (ref "C4") (pin "2") (pinfunction "2_2") (pintype "passive"))
      (node (ref "C5") (pin "2") (pinfunction "2_2") (pintype "passive"))
      (node (ref "C9") (pin "2") (pinfunction "2_2") (pintype "passive"))
      (node (ref "J1") (pin "4") (pinfunction "VTG_4") (pintype "passive"))
      (node (ref "U1") (pin "19") (pinfunction "VCC_19") (pintype "power_in"))
      (node (ref "U1") (pin "31") (pinfunction "VCC_31") (pintype "power_in"))
      (node (ref "U1") (pin "39") (pinfunction "AVCC_39") (pintype "power_in"))
      (node (ref "U1") (pin "9") (pinfunction "VCC_9") (pintype "power_in"))
      (node (ref "U2") (pin "3") (pinfunction "VccA_3") (pintype "power_in"))
      (node (ref "U2") (pin "6") (pinfunction "OE_6") (pintype "input"))
      (node (ref "U3") (pin "2") (pinfunction "VOUT_2") (pintype "power_in"))
      (node (ref "U3") (pin "4") (pinfunction "VOUT_4") (pintype "power_in"))
    )
    (net (code "177") (name "VDD") (class "Default")
      (node (ref "C11") (pin "2") (pinfunction "2_2") (pintype "passive"))
      (node (ref "C12") (pin "2") (pinfunction "2_2") (pintype "passive"))
      (node (ref "C13") (pin "2") (pinfunction "2_2") (pintype "passive"))
      (node (ref "C14") (pin "2") (pinfunction "2_2") (pintype "passive"))
      (node (ref "C15") (pin "2") (pinfunction "2_2") (pintype "passive"))
      (node (ref "C16") (pin "2") (pinfunction "2_2") (pintype "passive"))
      (node (ref "C17") (pin "2") (pinfunction "2_2") (pintype "passive"))
      (node (ref "C18") (pin "2") (pinfunction "2_2") (pintype "passive"))
      (node (ref "C19") (pin "2") (pinfunction "2_2") (pintype "passive"))
      (node (ref "C20") (pin "2") (pinfunction "2_2") (pintype "passive"))
      (node (ref "C21") (pin "2") (pinfunction "2_2") (pintype "passive"))
      (node (ref "C22") (pin "2") (pinfunction "2_2") (pintype "passive"))
      (node (ref "C23") (pin "2") (pinfunction "2_2") (pintype "passive"))
      (node (ref "C24") (pin "2") (pinfunction "2_2") (pintype "passive"))
      (node (ref "C25") (pin "2") (pinfunction "2_2") (pintype "passive"))
      (node (ref "C26") (pin "2") (pinfunction "2_2") (pintype "passive"))
      (node (ref "C27") (pin "2") (pinfunction "2_2") (pintype "passive"))
      (node (ref "C28") (pin "2") (pinfunction "2_2") (pintype "passive"))
      (node (ref "C29") (pin "2") (pinfunction "2_2") (pintype "passive"))
      (node (ref "C6") (pin "2") (pinfunction "2_2") (pintype "passive"))
      (node (ref "C7") (pin "2") (pinfunction "2_2") (pintype "passive"))
      (node (ref "C8") (pin "2") (pinfunction "2_2") (pintype "passive"))
      (node (ref "D1") (pin "1") (pinfunction "VDD_1") (pintype "passive"))
      (node (ref "D10") (pin "1") (pinfunction "VDD_1") (pintype "passive"))
      (node (ref "D11") (pin "1") (pinfunction "VDD_1") (pintype "passive"))
      (node (ref "D12") (pin "1") (pinfunction "VDD_1") (pintype "passive"))
      (node (ref "D13") (pin "1") (pinfunction "VDD_1") (pintype "passive"))
      (node (ref "D14") (pin "1") (pinfunction "VDD_1") (pintype "passive"))
      (node (ref "D15") (pin "1") (pinfunction "VDD_1") (pintype "passive"))
      (node (ref "D16") (pin "1") (pinfunction "VDD_1") (pintype "passive"))
      (node (ref "D17") (pin "1") (pinfunction "VDD_1") (pintype "passive"))
      (node (ref "D18") (pin "1") (pinfunction "VDD_1") (pintype "passive"))
      (node (ref "D19") (pin "1") (pinfunction "VDD_1") (pintype "passive"))
      (node (ref "D2") (pin "1") (pinfunction "VDD_1") (pintype "passive"))
      (node (ref "D20") (pin "1") (pinfunction "VDD_1") (pintype "passive"))
      (node (ref "D21") (pin "1") (pinfunction "VDD_1") (pintype "passive"))
      (node (ref "D22") (pin "1") (pinfunction "VDD_1") (pintype "passive"))
      (node (ref "D23") (pin "1") (pinfunction "VDD_1") (pintype "passive"))
      (node (ref "D24") (pin "1") (pinfunction "VDD_1") (pintype "passive"))
      (node (ref "D25") (pin "1") (pinfunction "VDD_1") (pintype "passive"))
      (node (ref "D26") (pin "1") (pinfunction "VDD_1") (pintype "passive"))
      (node (ref "D27") (pin "1") (pinfunction "VDD_1") (pintype "passive"))
      (node (ref "D28") (pin "1") (pinfunction "VDD_1") (pintype "passive"))
      (node (ref "D29") (pin "1") (pinfunction "VDD_1") (pintype "passive"))
      (node (ref "D3") (pin "1") (pinfunction "VDD_1") (pintype "passive"))
      (node (ref "D30") (pin "1") (pinfunction "VDD_1") (pintype "passive"))
      (node (ref "D31") (pin "1") (pinfunction "VDD_1") (pintype "passive"))
      (node (ref "D32") (pin "1") (pinfunction "VDD_1") (pintype "passive"))
      (node (ref "D33") (pin "1") (pinfunction "VDD_1") (pintype "passive"))
      (node (ref "D34") (pin "1") (pinfunction "VDD_1") (pintype "passive"))
      (node (ref "D35") (pin "1") (pinfunction "VDD_1") (pintype "passive"))
      (node (ref "D36") (pin "1") (pinfunction "VDD_1") (pintype "passive"))
      (node (ref "D37") (pin "1") (pinfunction "VDD_1") (pintype "passive"))
      (node (ref "D38") (pin "1") (pinfunction "VDD_1") (pintype "passive"))
      (node (ref "D39") (pin "1") (pinfunction "VDD_1") (pintype "passive"))
      (node (ref "D4") (pin "1") (pinfunction "VDD_1") (pintype "passive"))
      (node (ref "D40") (pin "1") (pinfunction "VDD_1") (pintype "passive"))
      (node (ref "D41") (pin "1") (pinfunction "VDD_1") (pintype "passive"))
      (node (ref "D42") (pin "1") (pinfunction "VDD_1") (pintype "passive"))
      (node (ref "D43") (pin "1") (pinfunction "VDD_1") (pintype "passive"))
      (node (ref "D44") (pin "1") (pinfunction "VDD_1") (pintype "passive"))
      (node (ref "D45") (pin "1") (pinfunction "VDD_1") (pintype "passive"))
      (node (ref "D46") (pin "1") (pinfunction "VDD_1") (pintype "passive"))
      (node (ref "D47") (pin "1") (pinfunction "VDD_1") (pintype "passive"))
      (node (ref "D48") (pin "1") (pinfunction "VDD_1") (pintype "passive"))
      (node (ref "D49") (pin "1") (pinfunction "VDD_1") (pintype "passive"))
      (node (ref "D5") (pin "1") (pinfunction "VDD_1") (pintype "passive"))
      (node (ref "D50") (pin "1") (pinfunction "VDD_1") (pintype "passive"))
      (node (ref "D51") (pin "1") (pinfunction "VDD_1") (pintype "passive"))
      (node (ref "D52") (pin "1") (pinfunction "VDD_1") (pintype "passive"))
      (node (ref "D53") (pin "1") (pinfunction "VDD_1") (pintype "passive"))
      (node (ref "D54") (pin "1") (pinfunction "VDD_1") (pintype "passive"))
      (node (ref "D55") (pin "1") (pinfunction "VDD_1") (pintype "passive"))
      (node (ref "D56") (pin "1") (pinfunction "VDD_1") (pintype "passive"))
      (node (ref "D57") (pin "1") (pinfunction "VDD_1") (pintype "passive"))
      (node (ref "D58") (pin "1") (pinfunction "VDD_1") (pintype "passive"))
      (node (ref "D59") (pin "1") (pinfunction "VDD_1") (pintype "passive"))
      (node (ref "D6") (pin "1") (pinfunction "VDD_1") (pintype "passive"))
      (node (ref "D60") (pin "1") (pinfunction "VDD_1") (pintype "passive"))
      (node (ref "D61") (pin "1") (pinfunction "VDD_1") (pintype "passive"))
      (node (ref "D62") (pin "1") (pinfunction "VDD_1") (pintype "passive"))
      (node (ref "D63") (pin "1") (pinfunction "VDD_1") (pintype "passive"))
      (node (ref "D64") (pin "1") (pinfunction "VDD_1") (pintype "passive"))
      (node (ref "D65") (pin "1") (pinfunction "VDD_1") (pintype "passive"))
      (node (ref "D66") (pin "1") (pinfunction "VDD_1") (pintype "passive"))
      (node (ref "D67") (pin "1") (pinfunction "VDD_1") (pintype "passive"))
      (node (ref "D68") (pin "1") (pinfunction "VDD_1") (pintype "passive"))
      (node (ref "D69") (pin "1") (pinfunction "VDD_1") (pintype "passive"))
      (node (ref "D7") (pin "1") (pinfunction "VDD_1") (pintype "passive"))
      (node (ref "D70") (pin "1") (pinfunction "VDD_1") (pintype "passive"))
      (node (ref "D71") (pin "1") (pinfunction "VDD_1") (pintype "passive"))
      (node (ref "D72") (pin "1") (pinfunction "VDD_1") (pintype "passive"))
      (node (ref "D73") (pin "1") (pinfunction "VDD_1") (pintype "passive"))
      (node (ref "D74") (pin "1") (pinfunction "VDD_1") (pintype "passive"))
      (node (ref "D75") (pin "1") (pinfunction "VDD_1") (pintype "passive"))
      (node (ref "D76") (pin "1") (pinfunction "VDD_1") (pintype "passive"))
      (node (ref "D77") (pin "1") (pinfunction "VDD_1") (pintype "passive"))
      (node (ref "D78") (pin "1") (pinfunction "VDD_1") (pintype "passive"))
      (node (ref "D79") (pin "1") (pinfunction "VDD_1") (pintype "passive"))
      (node (ref "D8") (pin "1") (pinfunction "VDD_1") (pintype "passive"))
      (node (ref "D80") (pin "1") (pinfunction "VDD_1") (pintype "passive"))
      (node (ref "D81") (pin "1") (pinfunction "VDD_1") (pintype "passive"))
      (node (ref "D82") (pin "1") (pinfunction "VDD_1") (pintype "passive"))
      (node (ref "D9") (pin "1") (pinfunction "VDD_1") (pintype "passive"))
      (node (ref "SW1") (pin "1") (pinfunction "N.C_1") (pintype "passive"))
      (node (ref "U2") (pin "7") (pinfunction "VccB_7") (pintype "power_in"))
      (node (ref "U3") (pin "3") (pinfunction "VIN_3") (pintype "power_in"))
    )
    (net (code "178") (name "unconnected-(D82-CKO-Pad2)") (class "Default")
      (node (ref "D82") (pin "2") (pinfunction "CKO_2") (pintype "passive"))
    )
    (net (code "179") (name "unconnected-(D82-SDO-Pad3)") (class "Default")
      (node (ref "D82") (pin "3") (pinfunction "SDO_3") (pintype "passive"))
    )
    (net (code "180") (name "unconnected-(J1-NC-Pad7)") (class "Default")
      (node (ref "J1") (pin "7") (pinfunction "NC_7") (pintype "passive"))
    )
    (net (code "181") (name "unconnected-(J1-NC-Pad8)") (class "Default")
      (node (ref "J1") (pin "8") (pinfunction "NC_8") (pintype "passive"))
    )
    (net (code "182") (name "unconnected-(J1-TCK-Pad1)") (class "Default")
      (node (ref "J1") (pin "1") (pinfunction "TCK_1") (pintype "passive"))
    )
    (net (code "183") (name "unconnected-(J1-TDI-Pad9)") (class "Default")
      (node (ref "J1") (pin "9") (pinfunction "TDI_9") (pintype "passive"))
    )
    (net (code "184") (name "unconnected-(J1-TMS-Pad5)") (class "Default")
      (node (ref "J1") (pin "5") (pinfunction "TMS_5") (pintype "passive"))
    )
    (net (code "185") (name "unconnected-(J2-D+-Pad3)") (class "Default")
      (node (ref "J2") (pin "3") (pinfunction "D+_3") (pintype "passive"))
    )
    (net (code "186") (name "unconnected-(J2-D--Pad2)") (class "Default")
      (node (ref "J2") (pin "2") (pinfunction "D-_2") (pintype "passive"))
    )
    (net (code "187") (name "unconnected-(J2-ID-Pad4)") (class "Default")
      (node (ref "J2") (pin "4") (pinfunction "ID_4") (pintype "passive"))
    )
    (net (code "188") (name "unconnected-(U1-PA0{slash}SYNC{slash}ADC0{slash}AC0{slash}AREF-Pad40)") (class "Default")
      (node (ref "U1") (pin "40") (pinfunction "PA0/SYNC/ADC0/AC0/AREF_40") (pintype "bidirectional"))
    )
    (net (code "189") (name "unconnected-(U1-PA1{slash}SYNC{slash}ADC1{slash}AC1-Pad41)") (class "Default")
      (node (ref "U1") (pin "41") (pinfunction "PA1/SYNC/ADC1/AC1_41") (pintype "bidirectional"))
    )
    (net (code "190") (name "unconnected-(U1-PA2{slash}SYNC{slash}ASYNC{slash}ADC2{slash}AC2-Pad42)") (class "Default")
      (node (ref "U1") (pin "42") (pinfunction "PA2/SYNC/ASYNC/ADC2/AC2_42") (pintype "bidirectional"))
    )
    (net (code "191") (name "unconnected-(U1-PA3{slash}SYNC{slash}ADC3{slash}AC3-Pad43)") (class "Default")
      (node (ref "U1") (pin "43") (pinfunction "PA3/SYNC/ADC3/AC3_43") (pintype "bidirectional"))
    )
    (net (code "192") (name "unconnected-(U1-PA4{slash}SYNC{slash}ADC4{slash}AC4-Pad44)") (class "Default")
      (node (ref "U1") (pin "44") (pinfunction "PA4/SYNC/ADC4/AC4_44") (pintype "bidirectional"))
    )
    (net (code "193") (name "unconnected-(U1-PA5{slash}SYNC{slash}ADC5{slash}AC5-Pad1)") (class "Default")
      (node (ref "U1") (pin "1") (pinfunction "PA5/SYNC/ADC5/AC5_1") (pintype "bidirectional"))
    )
    (net (code "194") (name "unconnected-(U1-PA6{slash}SYNC{slash}ADC6{slash}AC6{slash}AC1OUT-Pad2)") (class "Default")
      (node (ref "U1") (pin "2") (pinfunction "PA6/SYNC/ADC6/AC6/AC1OUT_2") (pintype "bidirectional"))
    )
    (net (code "195") (name "unconnected-(U1-PA7{slash}SYNC{slash}ADC7{slash}AC7{slash}AC0OUT-Pad3)") (class "Default")
      (node (ref "U1") (pin "3") (pinfunction "PA7/SYNC/ADC7/AC7/AC0OUT_3") (pintype "bidirectional"))
    )
    (net (code "196") (name "unconnected-(U1-PB0{slash}SYNC{slash}ADC8{slash}AREF-Pad4)") (class "Default")
      (node (ref "U1") (pin "4") (pinfunction "PB0/SYNC/ADC8/AREF_4") (pintype "bidirectional"))
    )
    (net (code "197") (name "unconnected-(U1-PB1{slash}SYNC{slash}ADC9-Pad5)") (class "Default")
      (node (ref "U1") (pin "5") (pinfunction "PB1/SYNC/ADC9_5") (pintype "bidirectional"))
    )
    (net (code "198") (name "unconnected-(U1-PB2{slash}SYNC{slash}ASYNC{slash}ADC10{slash}DAC0-Pad6)") (class "Default")
      (node (ref "U1") (pin "6") (pinfunction "PB2/SYNC/ASYNC/ADC10/DAC0_6") (pintype "bidirectional"))
    )
    (net (code "199") (name "unconnected-(U1-PB3{slash}SYNC{slash}ADC11{slash}DAC1-Pad7)") (class "Default")
      (node (ref "U1") (pin "7") (pinfunction "PB3/SYNC/ADC11/DAC1_7") (pintype "bidirectional"))
    )
    (net (code "200") (name "unconnected-(U1-PC0{slash}SYNC{slash}OC0A{slash}~{OC0ALS}{slash}SDA{slash}SDAIN-Pad10)") (class "Default")
      (node (ref "U1") (pin "10") (pinfunction "PC0/SYNC/OC0A/~{OC0ALS}/SDA/SDAIN_10") (pintype "bidirectional"))
    )
    (net (code "201") (name "unconnected-(U1-PC1{slash}SYNC{slash}OC0B{slash}OC0AHS{slash}XCK0{slash}SCL{slash}SCLIN-Pad11)") (class "Default")
      (node (ref "U1") (pin "11") (pinfunction "PC1/SYNC/OC0B/OC0AHS/XCK0/SCL/SCLIN_11") (pintype "bidirectional"))
    )
    (net (code "202") (name "unconnected-(U1-PC2{slash}SYNC{slash}ASYNC{slash}OC0C{slash}~{OC0BLS}{slash}RXD0{slash}SDAOUT-Pad12)") (class "Default")
      (node (ref "U1") (pin "12") (pinfunction "PC2/SYNC/ASYNC/OC0C/~{OC0BLS}/RXD0/SDAOUT_12") (pintype "bidirectional"))
    )
    (net (code "203") (name "unconnected-(U1-PC3{slash}SYNC{slash}OC0D{slash}OC0BHS{slash}TXD0{slash}SCLOUT-Pad13)") (class "Default")
      (node (ref "U1") (pin "13") (pinfunction "PC3/SYNC/OC0D/OC0BHS/TXD0/SCLOUT_13") (pintype "bidirectional"))
    )
    (net (code "204") (name "unconnected-(U1-PD0{slash}SYNC{slash}OC0A-Pad20)") (class "Default")
      (node (ref "U1") (pin "20") (pinfunction "PD0/SYNC/OC0A_20") (pintype "bidirectional"))
    )
    (net (code "205") (name "unconnected-(U1-PD1{slash}SYNC{slash}OC0B{slash}XCK0-Pad21)") (class "Default")
      (node (ref "U1") (pin "21") (pinfunction "PD1/SYNC/OC0B/XCK0_21") (pintype "bidirectional"))
    )
    (net (code "206") (name "unconnected-(U1-PD2{slash}SYNC{slash}ASYNC{slash}OC0C{slash}RXD0-Pad22)") (class "Default")
      (node (ref "U1") (pin "22") (pinfunction "PD2/SYNC/ASYNC/OC0C/RXD0_22") (pintype "bidirectional"))
    )
    (net (code "207") (name "unconnected-(U1-PD3{slash}SYNC{slash}OC0D{slash}TXD0-Pad23)") (class "Default")
      (node (ref "U1") (pin "23") (pinfunction "PD3/SYNC/OC0D/TXD0_23") (pintype "bidirectional"))
    )
    (net (code "208") (name "unconnected-(U1-PD4{slash}SYNC{slash}OC1A{slash}~{SS}-Pad24)") (class "Default")
      (node (ref "U1") (pin "24") (pinfunction "PD4/SYNC/OC1A/~{SS}_24") (pintype "bidirectional"))
    )
    (net (code "209") (name "unconnected-(U1-PD6{slash}SYNC{slash}D-{slash}RXD1{slash}MISO-Pad26)") (class "Default")
      (node (ref "U1") (pin "26") (pinfunction "PD6/SYNC/D-/RXD1/MISO_26") (pintype "bidirectional"))
    )
    (net (code "210") (name "unconnected-(U1-PE0{slash}SYNC{slash}OC0A{slash}SDA-Pad28)") (class "Default")
      (node (ref "U1") (pin "28") (pinfunction "PE0/SYNC/OC0A/SDA_28") (pintype "bidirectional"))
    )
    (net (code "211") (name "unconnected-(U1-PE1{slash}SYNC{slash}OC0B{slash}XCK0{slash}SCL-Pad29)") (class "Default")
      (node (ref "U1") (pin "29") (pinfunction "PE1/SYNC/OC0B/XCK0/SCL_29") (pintype "bidirectional"))
    )
    (net (code "212") (name "unconnected-(U1-PE2{slash}SYNC{slash}ASYNC{slash}OC0C{slash}RXD0-Pad32)") (class "Default")
      (node (ref "U1") (pin "32") (pinfunction "PE2/SYNC/ASYNC/OC0C/RXD0_32") (pintype "bidirectional"))
    )
    (net (code "213") (name "unconnected-(U1-PE3{slash}SYNC{slash}OC0D{slash}TXD0-Pad33)") (class "Default")
      (node (ref "U1") (pin "33") (pinfunction "PE3/SYNC/OC0D/TXD0_33") (pintype "bidirectional"))
    )
    (net (code "214") (name "unconnected-(U1-PR0{slash}SYNC{slash}XTAL2{slash}TOSC2-Pad36)") (class "Default")
      (node (ref "U1") (pin "36") (pinfunction "PR0/SYNC/XTAL2/TOSC2_36") (pintype "bidirectional"))
    )
    (net (code "215") (name "unconnected-(U1-PR1{slash}SYNC{slash}XTAL1{slash}TOSC1-Pad37)") (class "Default")
      (node (ref "U1") (pin "37") (pinfunction "PR1/SYNC/XTAL1/TOSC1_37") (pintype "bidirectional"))
    )
  )
)
